# Z_sim_v2.net
KiCad netlist of a schematic drawn in EAGLE
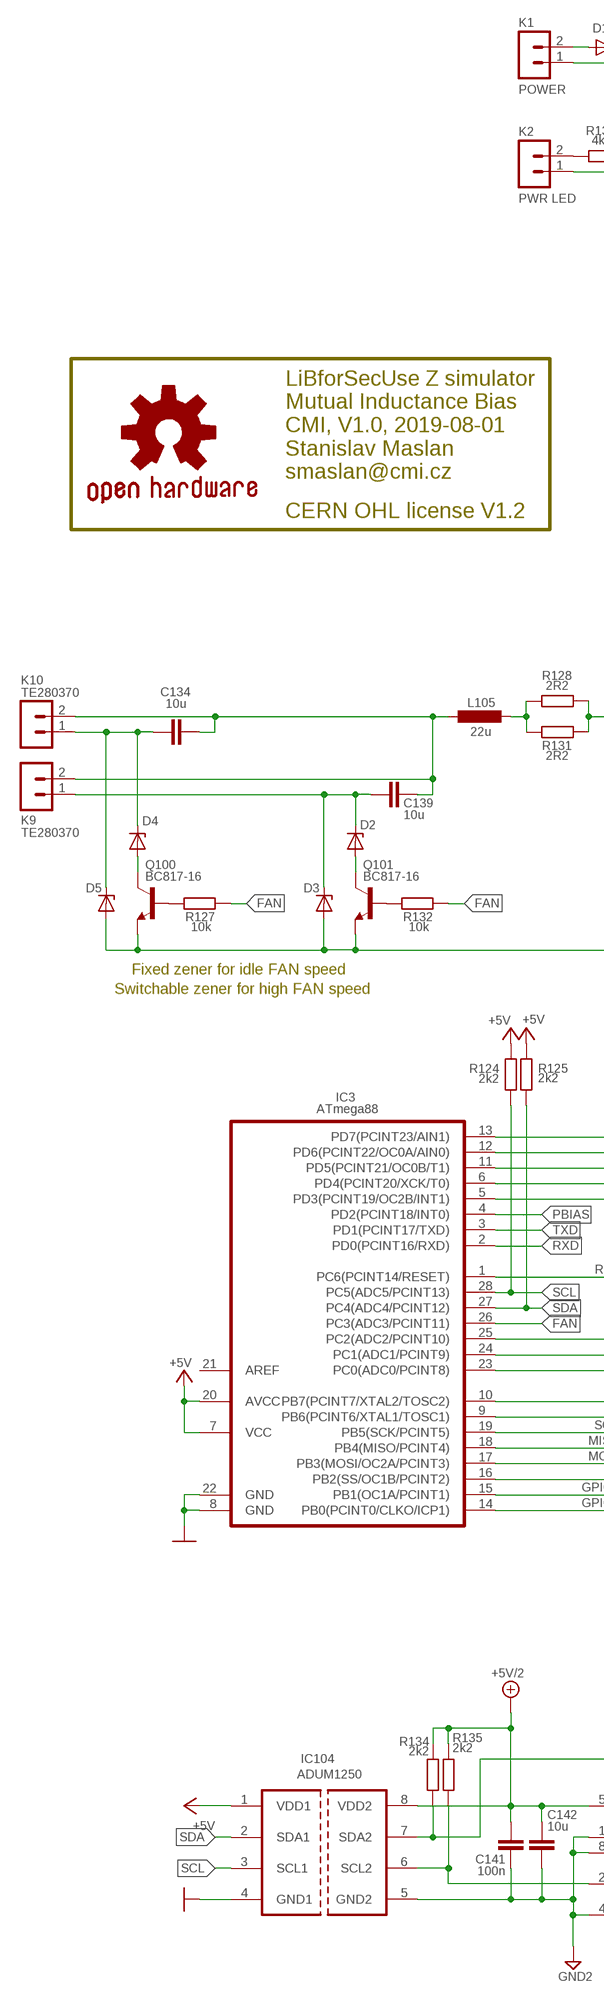
[diagram p0: schematic, sheet 1, part 1 of 2]
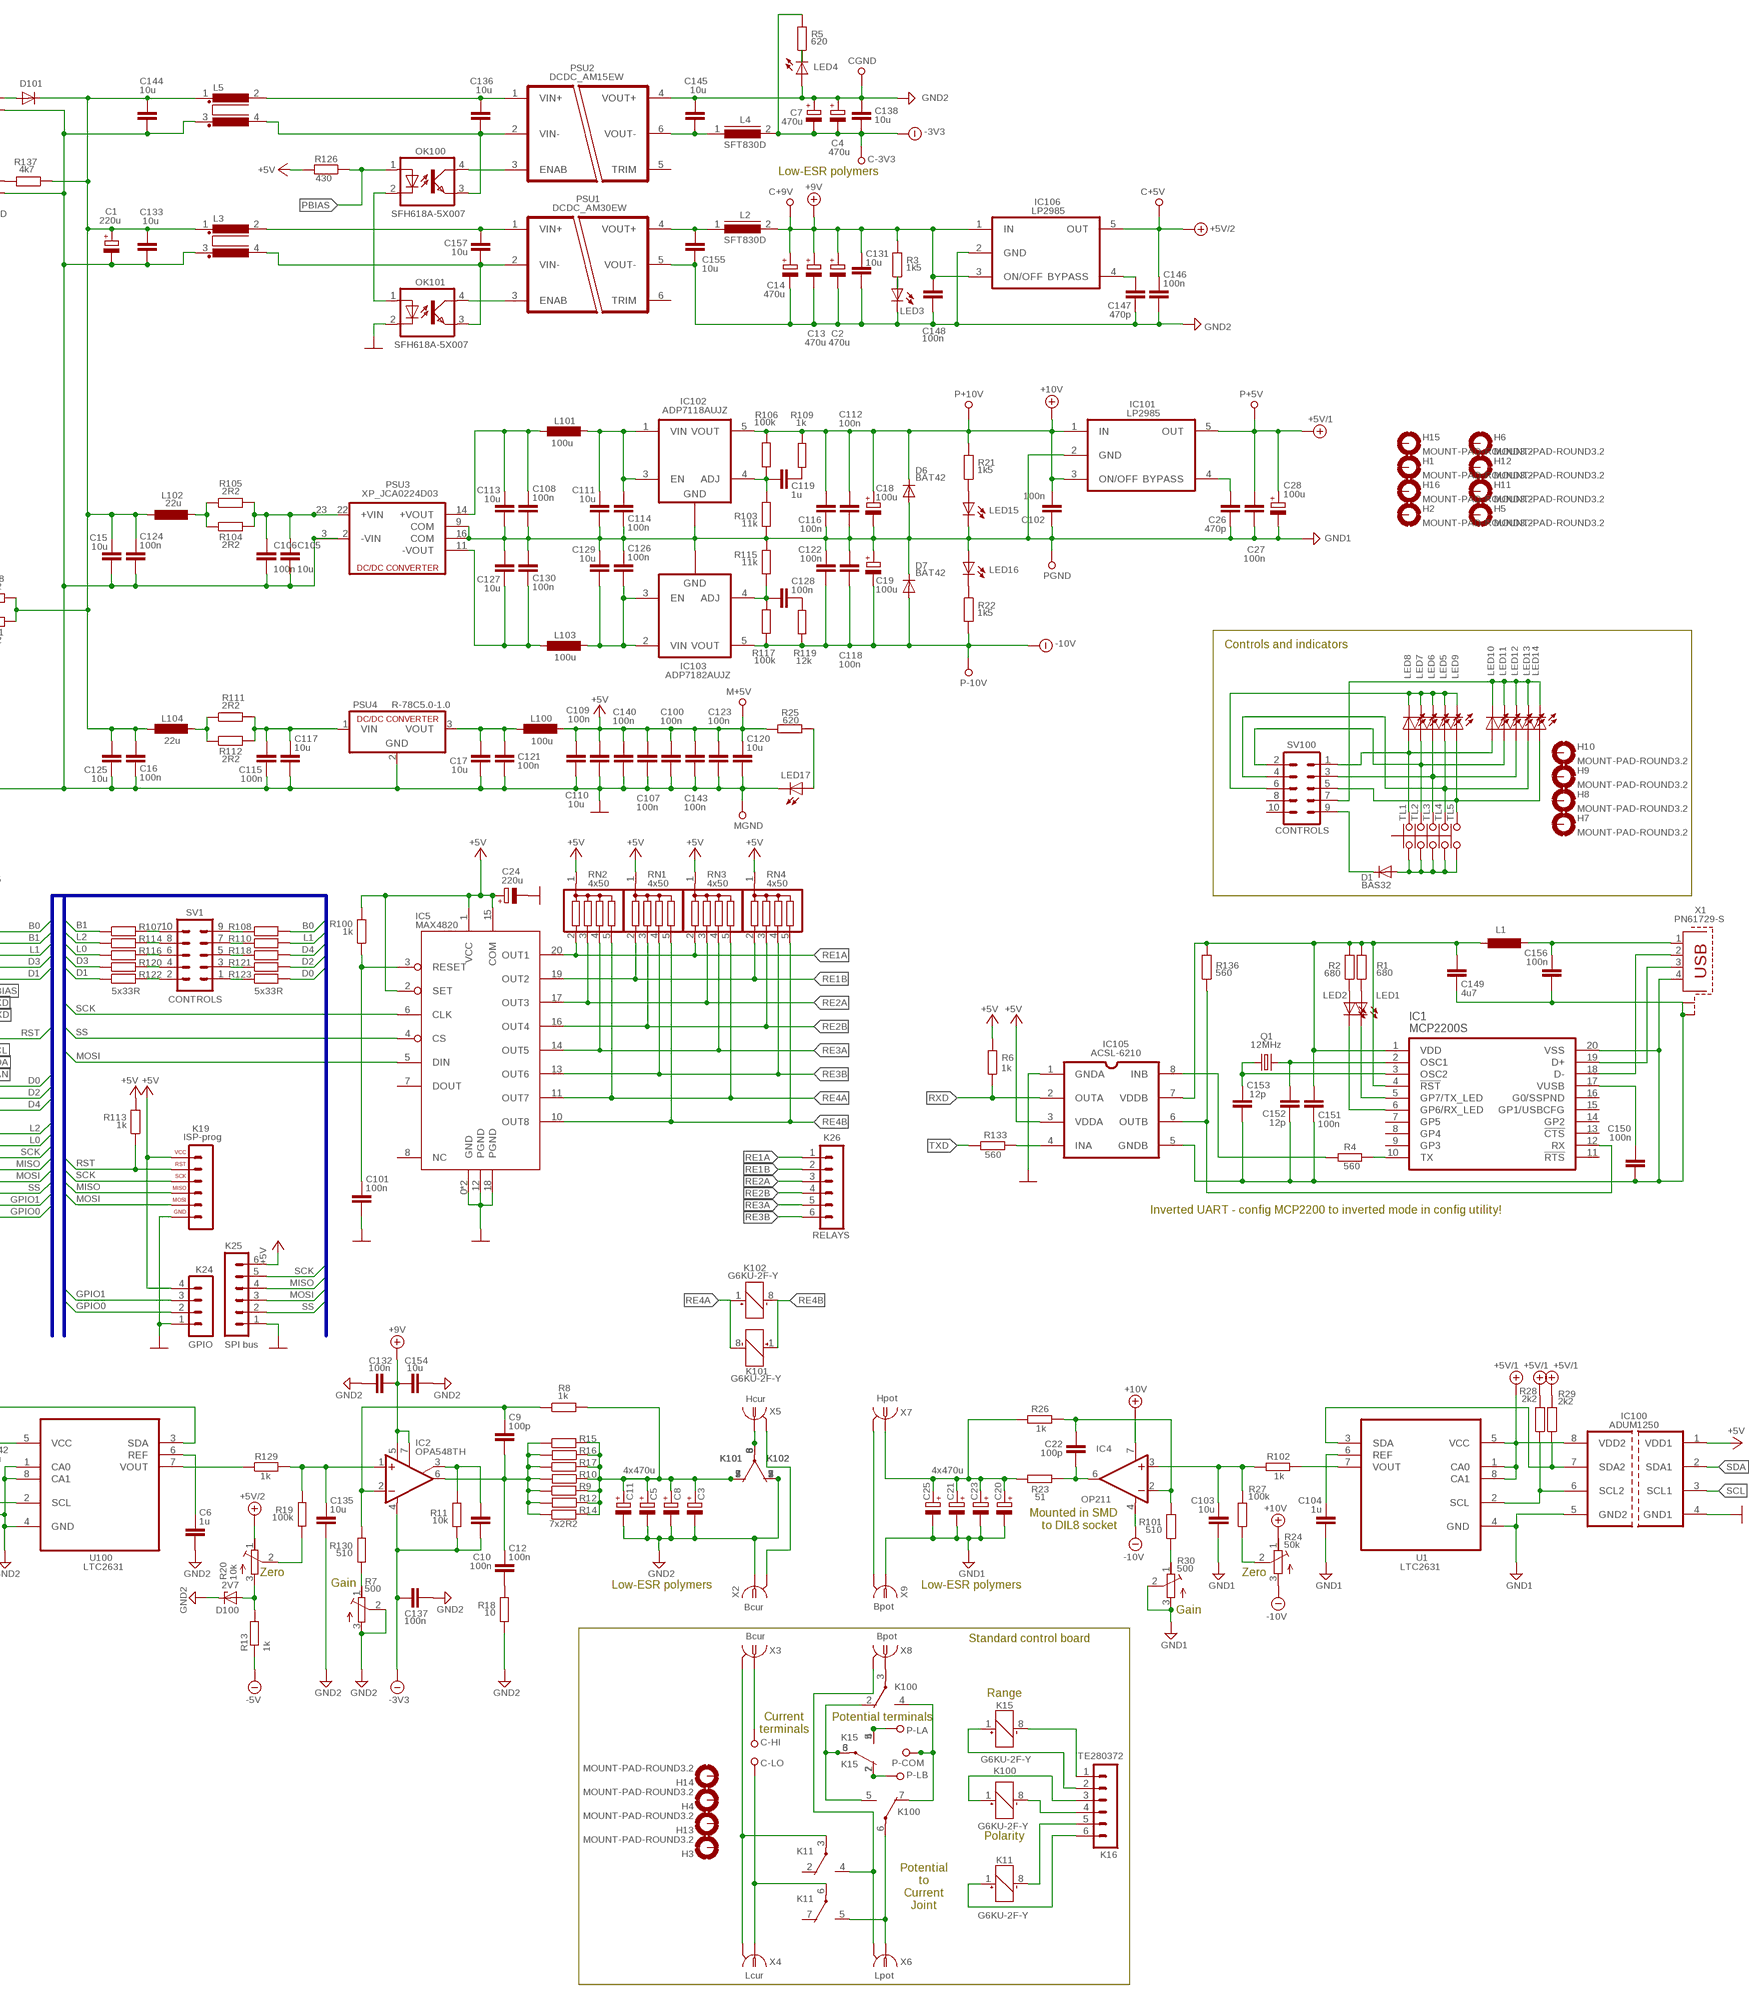
[diagram p1: schematic, sheet 1, part 2 of 2]

(export (version "E")
  (design (tool "Eeschema 10.0.6"))
  (components
    (comp (ref "C+5V")
      (value "SPL")
      (footprint "eagle-import:SP")
      (libsource (lib "eagle-import") (part "SPL"))
    )
    (comp (ref "C+9V")
      (value "SPL")
      (footprint "eagle-import:SP")
      (libsource (lib "eagle-import") (part "SPL"))
    )
    (comp (ref "C-3V3")
      (value "SPL")
      (footprint "eagle-import:SP")
      (libsource (lib "eagle-import") (part "SPL"))
    )
    (comp (ref "C-HI")
      (value "FAST28R")
      (footprint "eagle-import:FAST28_R")
      (libsource (lib "eagle-import") (part "FAST28R"))
    )
    (comp (ref "C-LO")
      (value "FAST28R")
      (footprint "eagle-import:FAST28_R")
      (libsource (lib "eagle-import") (part "FAST28R"))
    )
    (comp (ref "C1")
      (value "220u")
      (footprint "eagle-import:E3,5-8")
      (libsource (lib "eagle-import") (part "CPOL-EUE3.5-8"))
    )
    (comp (ref "C2")
      (value "470u")
      (footprint "eagle-import:E3,5-8")
      (libsource (lib "eagle-import") (part "CPOL-EUE3.5-8"))
    )
    (comp (ref "C3")
      (value "CPOL-EUE3.5-8")
      (footprint "eagle-import:E3,5-8")
      (libsource (lib "eagle-import") (part "CPOL-EUE3.5-8"))
    )
    (comp (ref "C4")
      (value "470u")
      (footprint "eagle-import:E3,5-8")
      (libsource (lib "eagle-import") (part "CPOL-EUE3.5-8"))
    )
    (comp (ref "C5")
      (value "CPOL-EUE3.5-8")
      (footprint "eagle-import:E3,5-8")
      (libsource (lib "eagle-import") (part "CPOL-EUE3.5-8"))
    )
    (comp (ref "C6")
      (value "1u")
      (footprint "eagle-import:X0805")
      (libsource (lib "eagle-import") (part "C-EUX0805"))
    )
    (comp (ref "C7")
      (value "470u")
      (footprint "eagle-import:E3,5-8")
      (libsource (lib "eagle-import") (part "CPOL-EUE3.5-8"))
    )
    (comp (ref "C8")
      (value "CPOL-EUE3.5-8")
      (footprint "eagle-import:E3,5-8")
      (libsource (lib "eagle-import") (part "CPOL-EUE3.5-8"))
    )
    (comp (ref "C9")
      (value "100p")
      (footprint "eagle-import:C025-024X044")
      (libsource (lib "eagle-import") (part "C-EU025-024X044"))
    )
    (comp (ref "C10")
      (value "100n")
      (footprint "eagle-import:X0805")
      (libsource (lib "eagle-import") (part "C-EUX0805"))
    )
    (comp (ref "C11")
      (value "4x470u")
      (footprint "eagle-import:E3,5-8")
      (libsource (lib "eagle-import") (part "CPOL-EUE3.5-8"))
    )
    (comp (ref "C12")
      (value "100n")
      (footprint "eagle-import:C050-024X044")
      (libsource (lib "eagle-import") (part "C-EU050-024X044"))
    )
    (comp (ref "C13")
      (value "470u")
      (footprint "eagle-import:E3,5-8")
      (libsource (lib "eagle-import") (part "CPOL-EUE3.5-8"))
    )
    (comp (ref "C14")
      (value "470u")
      (footprint "eagle-import:E3,5-8")
      (libsource (lib "eagle-import") (part "CPOL-EUE3.5-8"))
    )
    (comp (ref "C15")
      (value "10u")
      (footprint "eagle-import:C1210K")
      (libsource (lib "eagle-import") (part "C-EUC1210K"))
    )
    (comp (ref "C16")
      (value "100n")
      (footprint "eagle-import:X0805")
      (libsource (lib "eagle-import") (part "C-EUX0805"))
    )
    (comp (ref "C17")
      (value "10u")
      (footprint "eagle-import:C1210K")
      (libsource (lib "eagle-import") (part "C-EUC1210K"))
    )
    (comp (ref "C18")
      (value "100u")
      (footprint "eagle-import:E2,5-6")
      (libsource (lib "eagle-import") (part "CPOL-EUE2.5-6"))
    )
    (comp (ref "C19")
      (value "100u")
      (footprint "eagle-import:E2,5-6")
      (libsource (lib "eagle-import") (part "CPOL-EUE2.5-6"))
    )
    (comp (ref "C20")
      (value "CPOL-EUE3.5-8")
      (footprint "eagle-import:E3,5-8")
      (libsource (lib "eagle-import") (part "CPOL-EUE3.5-8"))
    )
    (comp (ref "C21")
      (value "CPOL-EUE3.5-8")
      (footprint "eagle-import:E3,5-8")
      (libsource (lib "eagle-import") (part "CPOL-EUE3.5-8"))
    )
    (comp (ref "C22")
      (value "100p")
      (footprint "eagle-import:C025-024X044")
      (libsource (lib "eagle-import") (part "C-EU025-024X044"))
    )
    (comp (ref "C23")
      (value "CPOL-EUE3.5-8")
      (footprint "eagle-import:E3,5-8")
      (libsource (lib "eagle-import") (part "CPOL-EUE3.5-8"))
    )
    (comp (ref "C24")
      (value "220u")
      (footprint "eagle-import:E3,5-8")
      (libsource (lib "eagle-import") (part "CPOL-EUE3.5-8"))
    )
    (comp (ref "C25")
      (value "4x470u")
      (footprint "eagle-import:E3,5-8")
      (libsource (lib "eagle-import") (part "CPOL-EUE3.5-8"))
    )
    (comp (ref "C26")
      (value "470p")
      (footprint "eagle-import:X0805")
      (libsource (lib "eagle-import") (part "C-EUX0805"))
    )
    (comp (ref "C27")
      (value "100n")
      (footprint "eagle-import:X0805")
      (libsource (lib "eagle-import") (part "C-EUX0805"))
    )
    (comp (ref "C28")
      (value "100u")
      (footprint "eagle-import:E2,5-6")
      (libsource (lib "eagle-import") (part "CPOL-EUE2.5-6"))
    )
    (comp (ref "C100")
      (value "100n")
      (footprint "eagle-import:X0805")
      (libsource (lib "eagle-import") (part "C-EUX0805"))
    )
    (comp (ref "C101")
      (value "100n")
      (footprint "eagle-import:X0805")
      (libsource (lib "eagle-import") (part "C-EUX0805"))
    )
    (comp (ref "C102")
      (value "100n")
      (footprint "eagle-import:X0805")
      (libsource (lib "eagle-import") (part "C-EUX0805"))
    )
    (comp (ref "C103")
      (value "10u")
      (footprint "eagle-import:C1210K")
      (libsource (lib "eagle-import") (part "C-EUC1210K"))
    )
    (comp (ref "C104")
      (value "1u")
      (footprint "eagle-import:X0805")
      (libsource (lib "eagle-import") (part "C-EUX0805"))
    )
    (comp (ref "C105")
      (value "10u")
      (footprint "eagle-import:C1210K")
      (libsource (lib "eagle-import") (part "C-EUC1210K"))
    )
    (comp (ref "C106")
      (value "100n")
      (footprint "eagle-import:X0805")
      (libsource (lib "eagle-import") (part "C-EUX0805"))
    )
    (comp (ref "C107")
      (value "100n")
      (footprint "eagle-import:X0805")
      (libsource (lib "eagle-import") (part "C-EUX0805"))
    )
    (comp (ref "C108")
      (value "100n")
      (footprint "eagle-import:X0805")
      (libsource (lib "eagle-import") (part "C-EUX0805"))
    )
    (comp (ref "C109")
      (value "100n")
      (footprint "eagle-import:X0805")
      (libsource (lib "eagle-import") (part "C-EUX0805"))
    )
    (comp (ref "C110")
      (value "10u")
      (footprint "eagle-import:C1210K")
      (libsource (lib "eagle-import") (part "C-EUC1210K"))
    )
    (comp (ref "C111")
      (value "10u")
      (footprint "eagle-import:C1210K")
      (libsource (lib "eagle-import") (part "C-EUC1210K"))
    )
    (comp (ref "C112")
      (value "100n")
      (footprint "eagle-import:X0805")
      (libsource (lib "eagle-import") (part "C-EUX0805"))
    )
    (comp (ref "C113")
      (value "10u")
      (footprint "eagle-import:C1210K")
      (libsource (lib "eagle-import") (part "C-EUC1210K"))
    )
    (comp (ref "C114")
      (value "100n")
      (footprint "eagle-import:X0805")
      (libsource (lib "eagle-import") (part "C-EUX0805"))
    )
    (comp (ref "C115")
      (value "100n")
      (footprint "eagle-import:X0805")
      (libsource (lib "eagle-import") (part "C-EUX0805"))
    )
    (comp (ref "C116")
      (value "100n")
      (footprint "eagle-import:X0805")
      (libsource (lib "eagle-import") (part "C-EUX0805"))
    )
    (comp (ref "C117")
      (value "10u")
      (footprint "eagle-import:C1210K")
      (libsource (lib "eagle-import") (part "C-EUC1210K"))
    )
    (comp (ref "C118")
      (value "100n")
      (footprint "eagle-import:X0805")
      (libsource (lib "eagle-import") (part "C-EUX0805"))
    )
    (comp (ref "C119")
      (value "1u")
      (footprint "eagle-import:X0805")
      (libsource (lib "eagle-import") (part "C-EUX0805"))
    )
    (comp (ref "C120")
      (value "10u")
      (footprint "eagle-import:C1210K")
      (libsource (lib "eagle-import") (part "C-EUC1210K"))
    )
    (comp (ref "C121")
      (value "100n")
      (footprint "eagle-import:X0805")
      (libsource (lib "eagle-import") (part "C-EUX0805"))
    )
    (comp (ref "C122")
      (value "100n")
      (footprint "eagle-import:X0805")
      (libsource (lib "eagle-import") (part "C-EUX0805"))
    )
    (comp (ref "C123")
      (value "100n")
      (footprint "eagle-import:X0805")
      (libsource (lib "eagle-import") (part "C-EUX0805"))
    )
    (comp (ref "C124")
      (value "100n")
      (footprint "eagle-import:X0805")
      (libsource (lib "eagle-import") (part "C-EUX0805"))
    )
    (comp (ref "C125")
      (value "10u")
      (footprint "eagle-import:C1210K")
      (libsource (lib "eagle-import") (part "C-EUC1210K"))
    )
    (comp (ref "C126")
      (value "100n")
      (footprint "eagle-import:X0805")
      (libsource (lib "eagle-import") (part "C-EUX0805"))
    )
    (comp (ref "C127")
      (value "10u")
      (footprint "eagle-import:C1210K")
      (libsource (lib "eagle-import") (part "C-EUC1210K"))
    )
    (comp (ref "C128")
      (value "100n")
      (footprint "eagle-import:X0805")
      (libsource (lib "eagle-import") (part "C-EUX0805"))
    )
    (comp (ref "C129")
      (value "10u")
      (footprint "eagle-import:C1210K")
      (libsource (lib "eagle-import") (part "C-EUC1210K"))
    )
    (comp (ref "C130")
      (value "100n")
      (footprint "eagle-import:X0805")
      (libsource (lib "eagle-import") (part "C-EUX0805"))
    )
    (comp (ref "C131")
      (value "10u")
      (footprint "eagle-import:C1210K")
      (libsource (lib "eagle-import") (part "C-EUC1210K"))
    )
    (comp (ref "C132")
      (value "100n")
      (footprint "eagle-import:X0805")
      (libsource (lib "eagle-import") (part "C-EUX0805"))
    )
    (comp (ref "C133")
      (value "10u")
      (footprint "eagle-import:C1210K")
      (libsource (lib "eagle-import") (part "C-EUC1210K"))
    )
    (comp (ref "C134")
      (value "10u")
      (footprint "eagle-import:C1210K")
      (libsource (lib "eagle-import") (part "C-EUC1210K"))
    )
    (comp (ref "C135")
      (value "10u")
      (footprint "eagle-import:C1210K")
      (libsource (lib "eagle-import") (part "C-EUC1210K"))
    )
    (comp (ref "C136")
      (value "10u")
      (footprint "eagle-import:C1210K")
      (libsource (lib "eagle-import") (part "C-EUC1210K"))
    )
    (comp (ref "C137")
      (value "100n")
      (footprint "eagle-import:X0805")
      (libsource (lib "eagle-import") (part "C-EUX0805"))
    )
    (comp (ref "C138")
      (value "10u")
      (footprint "eagle-import:C1210K")
      (libsource (lib "eagle-import") (part "C-EUC1210K"))
    )
    (comp (ref "C139")
      (value "10u")
      (footprint "eagle-import:C1210K")
      (libsource (lib "eagle-import") (part "C-EUC1210K"))
    )
    (comp (ref "C140")
      (value "100n")
      (footprint "eagle-import:X0805")
      (libsource (lib "eagle-import") (part "C-EUX0805"))
    )
    (comp (ref "C141")
      (value "100n")
      (footprint "eagle-import:X0805")
      (libsource (lib "eagle-import") (part "C-EUX0805"))
    )
    (comp (ref "C142")
      (value "10u")
      (footprint "eagle-import:C1210K")
      (libsource (lib "eagle-import") (part "C-EUC1210K"))
    )
    (comp (ref "C143")
      (value "100n")
      (footprint "eagle-import:X0805")
      (libsource (lib "eagle-import") (part "C-EUX0805"))
    )
    (comp (ref "C144")
      (value "10u")
      (footprint "eagle-import:C1210K")
      (libsource (lib "eagle-import") (part "C-EUC1210K"))
    )
    (comp (ref "C145")
      (value "10u")
      (footprint "eagle-import:C1210K")
      (libsource (lib "eagle-import") (part "C-EUC1210K"))
    )
    (comp (ref "C146")
      (value "100n")
      (footprint "eagle-import:X0805")
      (libsource (lib "eagle-import") (part "C-EUX0805"))
    )
    (comp (ref "C147")
      (value "470p")
      (footprint "eagle-import:X0805")
      (libsource (lib "eagle-import") (part "C-EUX0805"))
    )
    (comp (ref "C148")
      (value "100n")
      (footprint "eagle-import:X0805")
      (libsource (lib "eagle-import") (part "C-EUX0805"))
    )
    (comp (ref "C149")
      (value "4u7")
      (footprint "eagle-import:C1210K")
      (libsource (lib "eagle-import") (part "C-EUC1210K"))
    )
    (comp (ref "C150")
      (value "100n")
      (footprint "eagle-import:X0805")
      (libsource (lib "eagle-import") (part "C0805"))
    )
    (comp (ref "C151")
      (value "100n")
      (footprint "eagle-import:X0805")
      (libsource (lib "eagle-import") (part "C0805"))
    )
    (comp (ref "C152")
      (value "12p")
      (footprint "eagle-import:X0805")
      (libsource (lib "eagle-import") (part "C0805"))
    )
    (comp (ref "C153")
      (value "12p")
      (footprint "eagle-import:X0805")
      (libsource (lib "eagle-import") (part "C0805"))
    )
    (comp (ref "C154")
      (value "10u")
      (footprint "eagle-import:C1210K")
      (libsource (lib "eagle-import") (part "C-EUC1210K"))
    )
    (comp (ref "C155")
      (value "10u")
      (footprint "eagle-import:C1210K")
      (libsource (lib "eagle-import") (part "C-EUC1210K"))
    )
    (comp (ref "C156")
      (value "100n")
      (footprint "eagle-import:X0805")
      (libsource (lib "eagle-import") (part "C0805"))
    )
    (comp (ref "C157")
      (value "10u")
      (footprint "eagle-import:C1210K")
      (libsource (lib "eagle-import") (part "C-EUC1210K"))
    )
    (comp (ref "CGND")
      (value "SPL")
      (footprint "eagle-import:SP")
      (libsource (lib "eagle-import") (part "SPL"))
    )
    (comp (ref "D1")
      (value "BAS32")
      (footprint "eagle-import:SOD80C")
      (libsource (lib "eagle-import") (part "BAS32"))
    )
    (comp (ref "D2")
      (value "ZENER-DIODEZD-2.5")
      (footprint "eagle-import:ZDIO-2.5")
      (libsource (lib "eagle-import") (part "ZENER-DIODEZD-2.5"))
    )
    (comp (ref "D3")
      (value "ZENER-DIODEZD-2.5")
      (footprint "eagle-import:ZDIO-2.5")
      (libsource (lib "eagle-import") (part "ZENER-DIODEZD-2.5"))
    )
    (comp (ref "D4")
      (value "ZENER-DIODEZD-2.5")
      (footprint "eagle-import:ZDIO-2.5")
      (libsource (lib "eagle-import") (part "ZENER-DIODEZD-2.5"))
    )
    (comp (ref "D5")
      (value "ZENER-DIODEZD-2.5")
      (footprint "eagle-import:ZDIO-2.5")
      (libsource (lib "eagle-import") (part "ZENER-DIODEZD-2.5"))
    )
    (comp (ref "D6")
      (value "BAT42")
      (footprint "eagle-import:SOD80C")
      (libsource (lib "eagle-import") (part "DIODE-SOD80C"))
    )
    (comp (ref "D7")
      (value "BAT42")
      (footprint "eagle-import:SOD80C")
      (libsource (lib "eagle-import") (part "DIODE-SOD80C"))
    )
    (comp (ref "D100")
      (value "2V7")
      (footprint "eagle-import:SOD80C")
      (libsource (lib "eagle-import") (part "ZENER-DIODESOD80C"))
    )
    (comp (ref "D101")
      (value "DIODE-MELF-MLL41")
      (footprint "eagle-import:MELF-MLL41")
      (libsource (lib "eagle-import") (part "DIODE-MELF-MLL41"))
    )
    (comp (ref "GOLD_ORB_SM1")
      (value "OSHWLOGO_GOLD_ORB_MED")
      (footprint "eagle-import:OSHW1")
      (libsource (lib "eagle-import") (part "OSHWLOGO_GOLD_ORB_MED"))
    )
    (comp (ref "H1")
      (value "MOUNT-PAD-ROUND3.2")
      (footprint "eagle-import:3,2-PAD")
      (libsource (lib "eagle-import") (part "MOUNT-PAD-ROUND3.2"))
    )
    (comp (ref "H2")
      (value "MOUNT-PAD-ROUND3.2")
      (footprint "eagle-import:3,2-PAD")
      (libsource (lib "eagle-import") (part "MOUNT-PAD-ROUND3.2"))
    )
    (comp (ref "H3")
      (value "MOUNT-PAD-ROUND3.2")
      (footprint "eagle-import:3,2-PAD")
      (libsource (lib "eagle-import") (part "MOUNT-PAD-ROUND3.2"))
    )
    (comp (ref "H4")
      (value "MOUNT-PAD-ROUND3.2")
      (footprint "eagle-import:3,2-PAD")
      (libsource (lib "eagle-import") (part "MOUNT-PAD-ROUND3.2"))
    )
    (comp (ref "H5")
      (value "MOUNT-PAD-ROUND3.2")
      (footprint "eagle-import:3,2-PAD")
      (libsource (lib "eagle-import") (part "MOUNT-PAD-ROUND3.2"))
    )
    (comp (ref "H6")
      (value "MOUNT-PAD-ROUND3.2")
      (footprint "eagle-import:3,2-PAD")
      (libsource (lib "eagle-import") (part "MOUNT-PAD-ROUND3.2"))
    )
    (comp (ref "H7")
      (value "MOUNT-PAD-ROUND3.2")
      (footprint "eagle-import:3,2-PAD")
      (libsource (lib "eagle-import") (part "MOUNT-PAD-ROUND3.2"))
    )
    (comp (ref "H8")
      (value "MOUNT-PAD-ROUND3.2")
      (footprint "eagle-import:3,2-PAD")
      (libsource (lib "eagle-import") (part "MOUNT-PAD-ROUND3.2"))
    )
    (comp (ref "H9")
      (value "MOUNT-PAD-ROUND3.2")
      (footprint "eagle-import:3,2-PAD")
      (libsource (lib "eagle-import") (part "MOUNT-PAD-ROUND3.2"))
    )
    (comp (ref "H10")
      (value "MOUNT-PAD-ROUND3.2")
      (footprint "eagle-import:3,2-PAD")
      (libsource (lib "eagle-import") (part "MOUNT-PAD-ROUND3.2"))
    )
    (comp (ref "H11")
      (value "MOUNT-PAD-ROUND3.2")
      (footprint "eagle-import:3,2-PAD")
      (libsource (lib "eagle-import") (part "MOUNT-PAD-ROUND3.2"))
    )
    (comp (ref "H12")
      (value "MOUNT-PAD-ROUND3.2")
      (footprint "eagle-import:3,2-PAD")
      (libsource (lib "eagle-import") (part "MOUNT-PAD-ROUND3.2"))
    )
    (comp (ref "H13")
      (value "MOUNT-PAD-ROUND3.2")
      (footprint "eagle-import:3,2-PAD")
      (libsource (lib "eagle-import") (part "MOUNT-PAD-ROUND3.2"))
    )
    (comp (ref "H14")
      (value "MOUNT-PAD-ROUND3.2")
      (footprint "eagle-import:3,2-PAD")
      (libsource (lib "eagle-import") (part "MOUNT-PAD-ROUND3.2"))
    )
    (comp (ref "H15")
      (value "MOUNT-PAD-ROUND3.2")
      (footprint "eagle-import:3,2-PAD")
      (libsource (lib "eagle-import") (part "MOUNT-PAD-ROUND3.2"))
    )
    (comp (ref "H16")
      (value "MOUNT-PAD-ROUND3.2")
      (footprint "eagle-import:3,2-PAD")
      (libsource (lib "eagle-import") (part "MOUNT-PAD-ROUND3.2"))
    )
    (comp (ref "IC1")
      (value "MCP2200S")
      (footprint "eagle-import:SOIC20W")
      (libsource (lib "eagle-import") (part "MCP2200S"))
    )
    (comp (ref "IC2")
      (value "OPA548TH")
      (footprint "eagle-import:TO220-7H")
      (libsource (lib "eagle-import") (part "OPA548TH"))
    )
    (comp (ref "IC3")
      (value "ATmega88")
      (footprint "eagle-import:DIL28")
      (libsource (lib "eagle-import") (part "ATMEGA88P"))
    )
    (comp (ref "IC4")
      (value "OP211")
      (footprint "eagle-import:DIL08")
      (libsource (lib "eagle-import") (part "OPA650P"))
    )
    (comp (ref "IC5")
      (value "MAX4820")
      (footprint "eagle-import:TSSOP20")
      (libsource (lib "eagle-import") (part "MAX4820_TSSOP"))
    )
    (comp (ref "IC100")
      (value "ADUM1250")
      (footprint "eagle-import:SO8")
      (libsource (lib "eagle-import") (part "ADUM1250"))
    )
    (comp (ref "IC101")
      (value "LP2985")
      (footprint "eagle-import:SOT23-5")
      (libsource (lib "eagle-import") (part "LP2985"))
    )
    (comp (ref "IC102")
      (value "ADP7118AUJZ")
      (footprint "eagle-import:SOT23-5")
      (libsource (lib "eagle-import") (part "ADP7118AUJZ"))
    )
    (comp (ref "IC103")
      (value "ADP7182AUJZ")
      (footprint "eagle-import:SOT23-5")
      (libsource (lib "eagle-import") (part "ADP7182AUJZ"))
    )
    (comp (ref "IC104")
      (value "ADUM1250")
      (footprint "eagle-import:SO8")
      (libsource (lib "eagle-import") (part "ADUM1250"))
    )
    (comp (ref "IC105")
      (value "ACSL-6210")
      (footprint "eagle-import:SO8")
      (libsource (lib "eagle-import") (part "ACSL-6210"))
    )
    (comp (ref "IC106")
      (value "LP2985")
      (footprint "eagle-import:SOT23-5")
      (libsource (lib "eagle-import") (part "LP2985"))
    )
    (comp (ref "K1")
      (value "POWER")
      (footprint "eagle-import:TE280370")
      (libsource (lib "eagle-import") (part "TE280370"))
    )
    (comp (ref "K2")
      (value "PWR LED")
      (footprint "eagle-import:TE280370")
      (libsource (lib "eagle-import") (part "TE280370"))
    )
    (comp (ref "K9")
      (value "TE280370")
      (footprint "eagle-import:TE280370")
      (libsource (lib "eagle-import") (part "TE280370"))
    )
    (comp (ref "K10")
      (value "TE280370")
      (footprint "eagle-import:TE280370")
      (libsource (lib "eagle-import") (part "TE280370"))
    )
    (comp (ref "K11")
      (value "G6KU-2F-Y")
      (footprint "eagle-import:G6KU-2F-Y")
      (fields (field (name "MF") "OMRON COMPONENTS USA") (field (name "MPN") "G6KU-2F-Y DC3"))
      (libsource (lib "eagle-import") (part "G6KU-2F-Y"))
    )
    (comp (ref "K15")
      (value "G6KU-2F-Y")
      (footprint "eagle-import:G6KU-2F-Y")
      (fields (field (name "MF") "OMRON COMPONENTS USA") (field (name "MPN") "G6KU-2F-Y DC3"))
      (libsource (lib "eagle-import") (part "G6KU-2F-Y"))
    )
    (comp (ref "K16")
      (value "TE280372")
      (footprint "eagle-import:TE280372")
      (libsource (lib "eagle-import") (part "TE280372"))
    )
    (comp (ref "K19")
      (value "ISP-prog")
      (footprint "eagle-import:SIL6")
      (libsource (lib "eagle-import") (part "AVR_SPI"))
    )
    (comp (ref "K24")
      (value "GPIO")
      (footprint "eagle-import:TE280371")
      (libsource (lib "eagle-import") (part "TE280371"))
    )
    (comp (ref "K25")
      (value "SPI bus")
      (footprint "eagle-import:TE280372")
      (libsource (lib "eagle-import") (part "TE280372"))
    )
    (comp (ref "K26")
      (value "RELAYS")
      (footprint "eagle-import:TE280372")
      (libsource (lib "eagle-import") (part "TE280372"))
    )
    (comp (ref "K100")
      (value "G6KU-2F-Y")
      (footprint "eagle-import:G6KU-2F-Y")
      (fields (field (name "MF") "OMRON COMPONENTS USA") (field (name "MPN") "G6KU-2F-Y DC3"))
      (libsource (lib "eagle-import") (part "G6KU-2F-Y"))
    )
    (comp (ref "K101")
      (value "G6KU-2F-Y")
      (footprint "eagle-import:G6KU-2F-Y")
      (fields (field (name "MF") "OMRON COMPONENTS USA") (field (name "MPN") "G6KU-2F-Y DC3"))
      (libsource (lib "eagle-import") (part "G6KU-2F-Y"))
    )
    (comp (ref "K102")
      (value "G6KU-2F-Y")
      (footprint "eagle-import:G6KU-2F-Y")
      (fields (field (name "MF") "OMRON COMPONENTS USA") (field (name "MPN") "G6KU-2F-Y DC3"))
      (libsource (lib "eagle-import") (part "G6KU-2F-Y"))
    )
    (comp (ref "L1")
      (value "L-EU0204/5")
      (footprint "eagle-import:0204_5")
      (libsource (lib "eagle-import") (part "L-EU0204/5"))
    )
    (comp (ref "L2")
      (value "SFT830D")
      (footprint "eagle-import:SFT830D")
      (libsource (lib "eagle-import") (part "SFT830D"))
    )
    (comp (ref "L3")
      (value "R1405UB1/2")
      (footprint "eagle-import:B1_2")
      (libsource (lib "eagle-import") (part "R1405UB1/2"))
    )
    (comp (ref "L4")
      (value "SFT830D")
      (footprint "eagle-import:SFT830D")
      (libsource (lib "eagle-import") (part "SFT830D"))
    )
    (comp (ref "L5")
      (value "R1405UB1/2")
      (footprint "eagle-import:B1_2")
      (libsource (lib "eagle-import") (part "R1405UB1/2"))
    )
    (comp (ref "L100")
      (value "100u")
      (footprint "eagle-import:L1812")
      (libsource (lib "eagle-import") (part "L-EUL1812"))
    )
    (comp (ref "L101")
      (value "100u")
      (footprint "eagle-import:L1812")
      (libsource (lib "eagle-import") (part "L-EUL1812"))
    )
    (comp (ref "L102")
      (value "22u")
      (footprint "eagle-import:L1812")
      (libsource (lib "eagle-import") (part "L-EUL1812"))
    )
    (comp (ref "L103")
      (value "100u")
      (footprint "eagle-import:L1812")
      (libsource (lib "eagle-import") (part "L-EUL1812"))
    )
    (comp (ref "L104")
      (value "22u")
      (footprint "eagle-import:L1812")
      (libsource (lib "eagle-import") (part "L-EUL1812"))
    )
    (comp (ref "L105")
      (value "22u")
      (footprint "eagle-import:L1812")
      (libsource (lib "eagle-import") (part "L-EUL1812"))
    )
    (comp (ref "LED1")
      (value "LEDCHIP-LED0603")
      (footprint "eagle-import:CHIP-LED0603")
      (libsource (lib "eagle-import") (part "LEDCHIP-LED0603"))
    )
    (comp (ref "LED2")
      (value "LEDCHIP-LED0603")
      (footprint "eagle-import:CHIP-LED0603")
      (libsource (lib "eagle-import") (part "LEDCHIP-LED0603"))
    )
    (comp (ref "LED3")
      (value "LEDCHIP-LED0603")
      (footprint "eagle-import:CHIP-LED0603")
      (libsource (lib "eagle-import") (part "LEDCHIP-LED0603"))
    )
    (comp (ref "LED4")
      (value "LEDCHIP-LED0603")
      (footprint "eagle-import:CHIP-LED0603")
      (libsource (lib "eagle-import") (part "LEDCHIP-LED0603"))
    )
    (comp (ref "LED5")
      (value "LED3MM")
      (footprint "eagle-import:LED3MM")
      (libsource (lib "eagle-import") (part "LED3MM"))
    )
    (comp (ref "LED6")
      (value "LED3MM")
      (footprint "eagle-import:LED3MM")
      (libsource (lib "eagle-import") (part "LED3MM"))
    )
    (comp (ref "LED7")
      (value "LED3MM")
      (footprint "eagle-import:LED3MM")
      (libsource (lib "eagle-import") (part "LED3MM"))
    )
    (comp (ref "LED8")
      (value "LED3MM")
      (footprint "eagle-import:LED3MM")
      (libsource (lib "eagle-import") (part "LED3MM"))
    )
    (comp (ref "LED9")
      (value "LED3MM")
      (footprint "eagle-import:LED3MM")
      (libsource (lib "eagle-import") (part "LED3MM"))
    )
    (comp (ref "LED10")
      (value "LED3MM")
      (footprint "eagle-import:LED3MM")
      (libsource (lib "eagle-import") (part "LED3MM"))
    )
    (comp (ref "LED11")
      (value "LED3MM")
      (footprint "eagle-import:LED3MM")
      (libsource (lib "eagle-import") (part "LED3MM"))
    )
    (comp (ref "LED12")
      (value "LED3MM")
      (footprint "eagle-import:LED3MM")
      (libsource (lib "eagle-import") (part "LED3MM"))
    )
    (comp (ref "LED13")
      (value "LED3MM")
      (footprint "eagle-import:LED3MM")
      (libsource (lib "eagle-import") (part "LED3MM"))
    )
    (comp (ref "LED14")
      (value "LED3MM")
      (footprint "eagle-import:LED3MM")
      (libsource (lib "eagle-import") (part "LED3MM"))
    )
    (comp (ref "LED15")
      (value "LEDCHIP-LED0603")
      (footprint "eagle-import:CHIP-LED0603")
      (libsource (lib "eagle-import") (part "LEDCHIP-LED0603"))
    )
    (comp (ref "LED16")
      (value "LEDCHIP-LED0603")
      (footprint "eagle-import:CHIP-LED0603")
      (libsource (lib "eagle-import") (part "LEDCHIP-LED0603"))
    )
    (comp (ref "LED17")
      (value "LEDCHIP-LED0603")
      (footprint "eagle-import:CHIP-LED0603")
      (libsource (lib "eagle-import") (part "LEDCHIP-LED0603"))
    )
    (comp (ref "M+5V")
      (value "SPL")
      (footprint "eagle-import:SP")
      (libsource (lib "eagle-import") (part "SPL"))
    )
    (comp (ref "MGND")
      (value "SPL")
      (footprint "eagle-import:SP")
      (libsource (lib "eagle-import") (part "SPL"))
    )
    (comp (ref "OK100")
      (value "SFH618A-5X007")
      (footprint "eagle-import:SMD4-7")
      (libsource (lib "eagle-import") (part "SFH618?A-5X007"))
    )
    (comp (ref "OK101")
      (value "SFH618A-5X007")
      (footprint "eagle-import:SMD4-7")
      (libsource (lib "eagle-import") (part "SFH618?A-5X007"))
    )
    (comp (ref "P+5V")
      (value "SPL")
      (footprint "eagle-import:SP")
      (libsource (lib "eagle-import") (part "SPL"))
    )
    (comp (ref "P+10V")
      (value "SPL")
      (footprint "eagle-import:SP")
      (libsource (lib "eagle-import") (part "SPL"))
    )
    (comp (ref "P-10V")
      (value "SPL")
      (footprint "eagle-import:SP")
      (libsource (lib "eagle-import") (part "SPL"))
    )
    (comp (ref "P-COM")
      (value "FAST28R")
      (footprint "eagle-import:FAST28_R")
      (libsource (lib "eagle-import") (part "FAST28R"))
    )
    (comp (ref "P-LA")
      (value "FAST28R")
      (footprint "eagle-import:FAST28_R")
      (libsource (lib "eagle-import") (part "FAST28R"))
    )
    (comp (ref "P-LB")
      (value "FAST28R")
      (footprint "eagle-import:FAST28_R")
      (libsource (lib "eagle-import") (part "FAST28R"))
    )
    (comp (ref "PGND")
      (value "SPL")
      (footprint "eagle-import:SP")
      (libsource (lib "eagle-import") (part "SPL"))
    )
    (comp (ref "PSU1")
      (value "DCDC_AM30EW")
      (footprint "eagle-import:DCDC_AM30EW")
      (libsource (lib "eagle-import") (part "DCDC_AM30EW"))
    )
    (comp (ref "PSU2")
      (value "DCDC_AM15EW")
      (footprint "eagle-import:DCDC_AM15EW")
      (libsource (lib "eagle-import") (part "DCDC_AM15EW"))
    )
    (comp (ref "PSU3")
      (value "XP_JCA0224D03")
      (footprint "eagle-import:DCDC_XP_JCA_SYMOUT")
      (libsource (lib "eagle-import") (part "XP_JCA0224D03"))
    )
    (comp (ref "PSU4")
      (value "R-78C5.0-1.0")
      (footprint "eagle-import:SIP3")
      (libsource (lib "eagle-import") (part "R-78C-1.05.0"))
    )
    (comp (ref "Q1")
      (value "12MHz")
      (footprint "eagle-import:HC49_S")
      (libsource (lib "eagle-import") (part "CRYSTALHC49S"))
    )
    (comp (ref "Q100")
      (value "BC817-16")
      (footprint "eagle-import:SOT23-BEC")
      (libsource (lib "eagle-import") (part "BC817SMD-16LT1"))
    )
    (comp (ref "Q101")
      (value "BC817-16")
      (footprint "eagle-import:SOT23-BEC")
      (libsource (lib "eagle-import") (part "BC817SMD-16LT1"))
    )
    (comp (ref "R1")
      (value "680")
      (footprint "eagle-import:X0805")
      (libsource (lib "eagle-import") (part "R0805"))
    )
    (comp (ref "R2")
      (value "680")
      (footprint "eagle-import:X0805")
      (libsource (lib "eagle-import") (part "R0805"))
    )
    (comp (ref "R3")
      (value "1k5")
      (footprint "eagle-import:X0805")
      (libsource (lib "eagle-import") (part "R0805"))
    )
    (comp (ref "R4")
      (value "560")
      (footprint "eagle-import:X0805")
      (libsource (lib "eagle-import") (part "R0805"))
    )
    (comp (ref "R5")
      (value "620")
      (footprint "eagle-import:X0805")
      (libsource (lib "eagle-import") (part "R0805"))
    )
    (comp (ref "R6")
      (value "1k")
      (footprint "eagle-import:X0805")
      (libsource (lib "eagle-import") (part "R0805"))
    )
    (comp (ref "R7")
      (value "500")
      (footprint "eagle-import:RTRIMT93YB")
      (libsource (lib "eagle-import") (part "R-TRIMMT93YB"))
    )
    (comp (ref "R8")
      (value "1k")
      (footprint "eagle-import:0207_2V")
      (libsource (lib "eagle-import") (part "R-EU_0207/2V"))
    )
    (comp (ref "R9")
      (value "R-EU_0207/2V")
      (footprint "eagle-import:0207_2V")
      (libsource (lib "eagle-import") (part "R-EU_0207/2V"))
    )
    (comp (ref "R10")
      (value "R-EU_0207/2V")
      (footprint "eagle-import:0207_2V")
      (libsource (lib "eagle-import") (part "R-EU_0207/2V"))
    )
    (comp (ref "R11")
      (value "10k")
      (footprint "eagle-import:X0805")
      (libsource (lib "eagle-import") (part "R-EU_X0805"))
    )
    (comp (ref "R12")
      (value "7x2R2")
      (footprint "eagle-import:0207_2V")
      (libsource (lib "eagle-import") (part "R-EU_0207/2V"))
    )
    (comp (ref "R13")
      (value "1k")
      (footprint "eagle-import:X0805")
      (libsource (lib "eagle-import") (part "R-EU_X0805"))
    )
    (comp (ref "R14")
      (value "R-EU_0207/2V")
      (footprint "eagle-import:0207_2V")
      (libsource (lib "eagle-import") (part "R-EU_0207/2V"))
    )
    (comp (ref "R15")
      (value "R-EU_0207/2V")
      (footprint "eagle-import:0207_2V")
      (libsource (lib "eagle-import") (part "R-EU_0207/2V"))
    )
    (comp (ref "R16")
      (value "R-EU_0207/2V")
      (footprint "eagle-import:0207_2V")
      (libsource (lib "eagle-import") (part "R-EU_0207/2V"))
    )
    (comp (ref "R17")
      (value "R-EU_0207/2V")
      (footprint "eagle-import:0207_2V")
      (libsource (lib "eagle-import") (part "R-EU_0207/2V"))
    )
    (comp (ref "R18")
      (value "10")
      (footprint "eagle-import:0207_2V")
      (libsource (lib "eagle-import") (part "R-EU_0207/2V"))
    )
    (comp (ref "R19")
      (value "100k")
      (footprint "eagle-import:0204V")
      (libsource (lib "eagle-import") (part "R-EU_0204/2V"))
    )
    (comp (ref "R20")
      (value "10k")
      (footprint "eagle-import:RTRIMT93YB")
      (libsource (lib "eagle-import") (part "R-TRIMMT93YB"))
    )
    (comp (ref "R21")
      (value "1k5")
      (footprint "eagle-import:X0805")
      (libsource (lib "eagle-import") (part "R0805"))
    )
    (comp (ref "R22")
      (value "1k5")
      (footprint "eagle-import:X0805")
      (libsource (lib "eagle-import") (part "R0805"))
    )
    (comp (ref "R23")
      (value "51")
      (footprint "eagle-import:0207_2V")
      (libsource (lib "eagle-import") (part "R-EU_0207/2V"))
    )
    (comp (ref "R24")
      (value "50k")
      (footprint "eagle-import:RTRIMT93YB")
      (libsource (lib "eagle-import") (part "R-TRIMMT93YB"))
    )
    (comp (ref "R25")
      (value "620")
      (footprint "eagle-import:X0805")
      (libsource (lib "eagle-import") (part "R0805"))
    )
    (comp (ref "R26")
      (value "1k")
      (footprint "eagle-import:0207_2V")
      (libsource (lib "eagle-import") (part "R-EU_0207/2V"))
    )
    (comp (ref "R27")
      (value "100k")
      (footprint "eagle-import:0204V")
      (libsource (lib "eagle-import") (part "R-EU_0204/2V"))
    )
    (comp (ref "R28")
      (value "2k2")
      (footprint "eagle-import:X0805")
      (libsource (lib "eagle-import") (part "R-EU_X0805"))
    )
    (comp (ref "R29")
      (value "2k2")
      (footprint "eagle-import:X0805")
      (libsource (lib "eagle-import") (part "R-EU_X0805"))
    )
    (comp (ref "R30")
      (value "500")
      (footprint "eagle-import:RTRIMT93YB")
      (libsource (lib "eagle-import") (part "R-TRIMMT93YB"))
    )
    (comp (ref "R100")
      (value "1k")
      (footprint "eagle-import:X0805")
      (libsource (lib "eagle-import") (part "R0805"))
    )
    (comp (ref "R101")
      (value "510")
      (footprint "eagle-import:X0805")
      (libsource (lib "eagle-import") (part "R-EU_X0805"))
    )
    (comp (ref "R102")
      (value "1k")
      (footprint "eagle-import:X0805")
      (libsource (lib "eagle-import") (part "R-EU_X0805"))
    )
    (comp (ref "R103")
      (value "11k")
      (footprint "eagle-import:X0805")
      (libsource (lib "eagle-import") (part "R-EU_X0805"))
    )
    (comp (ref "R104")
      (value "2R2")
      (footprint "eagle-import:X0805")
      (libsource (lib "eagle-import") (part "R-EU_X0805"))
    )
    (comp (ref "R105")
      (value "2R2")
      (footprint "eagle-import:X0805")
      (libsource (lib "eagle-import") (part "R-EU_X0805"))
    )
    (comp (ref "R106")
      (value "100k")
      (footprint "eagle-import:X0805")
      (libsource (lib "eagle-import") (part "R-EU_X0805"))
    )
    (comp (ref "R107")
      (value "5x33R")
      (footprint "eagle-import:X0805")
      (libsource (lib "eagle-import") (part "R-EU_X0805"))
    )
    (comp (ref "R108")
      (value "R-EU_X0805")
      (footprint "eagle-import:X0805")
      (libsource (lib "eagle-import") (part "R-EU_X0805"))
    )
    (comp (ref "R109")
      (value "1k")
      (footprint "eagle-import:X0805")
      (libsource (lib "eagle-import") (part "R-EU_X0805"))
    )
    (comp (ref "R110")
      (value "R-EU_X0805")
      (footprint "eagle-import:X0805")
      (libsource (lib "eagle-import") (part "R-EU_X0805"))
    )
    (comp (ref "R111")
      (value "2R2")
      (footprint "eagle-import:X0805")
      (libsource (lib "eagle-import") (part "R-EU_X0805"))
    )
    (comp (ref "R112")
      (value "2R2")
      (footprint "eagle-import:X0805")
      (libsource (lib "eagle-import") (part "R-EU_X0805"))
    )
    (comp (ref "R113")
      (value "1k")
      (footprint "eagle-import:X0805")
      (libsource (lib "eagle-import") (part "R0805"))
    )
    (comp (ref "R114")
      (value "R-EU_X0805")
      (footprint "eagle-import:X0805")
      (libsource (lib "eagle-import") (part "R-EU_X0805"))
    )
    (comp (ref "R115")
      (value "11k")
      (footprint "eagle-import:X0805")
      (libsource (lib "eagle-import") (part "R-EU_X0805"))
    )
    (comp (ref "R116")
      (value "R-EU_X0805")
      (footprint "eagle-import:X0805")
      (libsource (lib "eagle-import") (part "R-EU_X0805"))
    )
    (comp (ref "R117")
      (value "100k")
      (footprint "eagle-import:X0805")
      (libsource (lib "eagle-import") (part "R-EU_X0805"))
    )
    (comp (ref "R118")
      (value "R-EU_X0805")
      (footprint "eagle-import:X0805")
      (libsource (lib "eagle-import") (part "R-EU_X0805"))
    )
    (comp (ref "R119")
      (value "12k")
      (footprint "eagle-import:X0805")
      (libsource (lib "eagle-import") (part "R-EU_X0805"))
    )
    (comp (ref "R120")
      (value "R-EU_X0805")
      (footprint "eagle-import:X0805")
      (libsource (lib "eagle-import") (part "R-EU_X0805"))
    )
    (comp (ref "R121")
      (value "R-EU_X0805")
      (footprint "eagle-import:X0805")
      (libsource (lib "eagle-import") (part "R-EU_X0805"))
    )
    (comp (ref "R122")
      (value "R-EU_X0805")
      (footprint "eagle-import:X0805")
      (libsource (lib "eagle-import") (part "R-EU_X0805"))
    )
    (comp (ref "R123")
      (value "5x33R")
      (footprint "eagle-import:X0805")
      (libsource (lib "eagle-import") (part "R-EU_X0805"))
    )
    (comp (ref "R124")
      (value "2k2")
      (footprint "eagle-import:X0805")
      (libsource (lib "eagle-import") (part "R0805"))
    )
    (comp (ref "R125")
      (value "2k2")
      (footprint "eagle-import:X0805")
      (libsource (lib "eagle-import") (part "R0805"))
    )
    (comp (ref "R126")
      (value "430")
      (footprint "eagle-import:X0805")
      (libsource (lib "eagle-import") (part "R-EU_X0805"))
    )
    (comp (ref "R127")
      (value "10k")
      (footprint "eagle-import:X0805")
      (libsource (lib "eagle-import") (part "R0805"))
    )
    (comp (ref "R128")
      (value "2R2")
      (footprint "eagle-import:X0805")
      (libsource (lib "eagle-import") (part "R-EU_X0805"))
    )
    (comp (ref "R129")
      (value "1k")
      (footprint "eagle-import:X0805")
      (libsource (lib "eagle-import") (part "R-EU_X0805"))
    )
    (comp (ref "R130")
      (value "510")
      (footprint "eagle-import:X0805")
      (libsource (lib "eagle-import") (part "R-EU_X0805"))
    )
    (comp (ref "R131")
      (value "2R2")
      (footprint "eagle-import:X0805")
      (libsource (lib "eagle-import") (part "R-EU_X0805"))
    )
    (comp (ref "R132")
      (value "10k")
      (footprint "eagle-import:X0805")
      (libsource (lib "eagle-import") (part "R0805"))
    )
    (comp (ref "R133")
      (value "560")
      (footprint "eagle-import:X0805")
      (libsource (lib "eagle-import") (part "R0805"))
    )
    (comp (ref "R134")
      (value "2k2")
      (footprint "eagle-import:X0805")
      (libsource (lib "eagle-import") (part "R-EU_X0805"))
    )
    (comp (ref "R135")
      (value "2k2")
      (footprint "eagle-import:X0805")
      (libsource (lib "eagle-import") (part "R-EU_X0805"))
    )
    (comp (ref "R136")
      (value "560")
      (footprint "eagle-import:X0805")
      (libsource (lib "eagle-import") (part "R0805"))
    )
    (comp (ref "R137")
      (value "4k7")
      (footprint "eagle-import:X0805")
      (libsource (lib "eagle-import") (part "R-EU_X0805"))
    )
    (comp (ref "RN1")
      (value "4x50")
      (footprint "eagle-import:SIL5")
      (libsource (lib "eagle-import") (part "G04R"))
    )
    (comp (ref "RN2")
      (value "4x50")
      (footprint "eagle-import:SIL5")
      (libsource (lib "eagle-import") (part "G04R"))
    )
    (comp (ref "RN3")
      (value "4x50")
      (footprint "eagle-import:SIL5")
      (libsource (lib "eagle-import") (part "G04R"))
    )
    (comp (ref "RN4")
      (value "4x50")
      (footprint "eagle-import:SIL5")
      (libsource (lib "eagle-import") (part "G04R"))
    )
    (comp (ref "SV1")
      (value "CONTROLS")
      (footprint "eagle-import:ML10")
      (libsource (lib "eagle-import") (part "ML10"))
    )
    (comp (ref "SV100")
      (value "CONTROLS")
      (footprint "eagle-import:ML10")
      (libsource (lib "eagle-import") (part "ML10"))
    )
    (comp (ref "TL1")
      (value "CUDL1_A")
      (footprint "eagle-import:CUDL1")
      (libsource (lib "eagle-import") (part "CUDL1_A"))
    )
    (comp (ref "TL2")
      (value "CUDL1_A")
      (footprint "eagle-import:CUDL1")
      (libsource (lib "eagle-import") (part "CUDL1_A"))
    )
    (comp (ref "TL3")
      (value "CUDL1_A")
      (footprint "eagle-import:CUDL1")
      (libsource (lib "eagle-import") (part "CUDL1_A"))
    )
    (comp (ref "TL4")
      (value "CUDL1_A")
      (footprint "eagle-import:CUDL1")
      (libsource (lib "eagle-import") (part "CUDL1_A"))
    )
    (comp (ref "TL5")
      (value "CUDL1_A")
      (footprint "eagle-import:CUDL1")
      (libsource (lib "eagle-import") (part "CUDL1_A"))
    )
    (comp (ref "U1")
      (value "LTC2631")
      (footprint "eagle-import:SOT65P280X100-8N")
      (fields (field (name "MPN") "LTC2631AITS8-LZ12#PBF"))
      (libsource (lib "eagle-import") (part "LTC2631AITS8-LZ12PBF"))
    )
    (comp (ref "U100")
      (value "LTC2631")
      (footprint "eagle-import:SOT65P280X100-8N")
      (fields (field (name "MPN") "LTC2631AITS8-LZ12#PBF"))
      (libsource (lib "eagle-import") (part "LTC2631AITS8-LZ12PBF"))
    )
    (comp (ref "X1")
      (value "PN61729-S")
      (footprint "eagle-import:PN61729-S")
      (libsource (lib "eagle-import") (part "PN61729-S"))
    )
    (comp (ref "X2")
      (value "Bcur")
      (footprint "eagle-import:A1944")
      (libsource (lib "eagle-import") (part "A1944-50"))
    )
    (comp (ref "X3")
      (value "Bcur")
      (footprint "eagle-import:A1944")
      (libsource (lib "eagle-import") (part "A1944-50"))
    )
    (comp (ref "X4")
      (value "Lcur")
      (footprint "eagle-import:A1944")
      (libsource (lib "eagle-import") (part "A1944-50"))
    )
    (comp (ref "X5")
      (value "Hcur")
      (footprint "eagle-import:A1944")
      (libsource (lib "eagle-import") (part "A1944-50"))
    )
    (comp (ref "X6")
      (value "Lpot")
      (footprint "eagle-import:A1944")
      (libsource (lib "eagle-import") (part "A1944-50"))
    )
    (comp (ref "X7")
      (value "Hpot")
      (footprint "eagle-import:A1944")
      (libsource (lib "eagle-import") (part "A1944-50"))
    )
    (comp (ref "X8")
      (value "Bpot")
      (footprint "eagle-import:A1944")
      (libsource (lib "eagle-import") (part "A1944-50"))
    )
    (comp (ref "X9")
      (value "Bpot")
      (footprint "eagle-import:A1944")
      (libsource (lib "eagle-import") (part "A1944-50"))
    )
  )
  (nets
    (net (code "1") (name "+5V") (class "Default")
      (node (ref "C100") (pin "P$1") (pinfunction "1_P$1") (pintype "passive"))
      (node (ref "C107") (pin "P$1") (pinfunction "1_P$1") (pintype "passive"))
      (node (ref "C109") (pin "P$1") (pinfunction "1_P$1") (pintype "passive"))
      (node (ref "C110") (pin "1") (pinfunction "1_1") (pintype "passive"))
      (node (ref "C120") (pin "1") (pinfunction "1_1") (pintype "passive"))
      (node (ref "C123") (pin "P$1") (pinfunction "1_P$1") (pintype "passive"))
      (node (ref "C140") (pin "P$1") (pinfunction "1_P$1") (pintype "passive"))
      (node (ref "C143") (pin "P$1") (pinfunction "1_P$1") (pintype "passive"))
      (node (ref "C24") (pin "+") (pinfunction "+_+") (pintype "passive"))
      (node (ref "IC100") (pin "1") (pinfunction "VDD1_1") (pintype "power_in"))
      (node (ref "IC104") (pin "1") (pinfunction "VDD1_1") (pintype "power_in"))
      (node (ref "IC105") (pin "3") (pinfunction "VDDA_3") (pintype "power_in"))
      (node (ref "IC3") (pin "20") (pinfunction "AVCC_20") (pintype "power_in"))
      (node (ref "IC3") (pin "7") (pinfunction "VCC_7") (pintype "power_in"))
      (node (ref "IC5") (pin "1") (pinfunction "VCC_1") (pintype "power_in"))
      (node (ref "IC5") (pin "15") (pinfunction "COM_15") (pintype "bidirectional"))
      (node (ref "IC5") (pin "2") (pinfunction "SET_2") (pintype "input"))
      (node (ref "K19") (pin "6") (pinfunction "6_6") (pintype "passive"))
      (node (ref "K24") (pin "4") (pinfunction "4_4") (pintype "passive"))
      (node (ref "K25") (pin "6") (pinfunction "6_6") (pintype "passive"))
      (node (ref "L100") (pin "2") (pinfunction "2_2") (pintype "passive"))
      (node (ref "M+5V") (pin "1") (pinfunction "P$1_1") (pintype "passive"))
      (node (ref "R100") (pin "P$2") (pinfunction "2_P$2") (pintype "passive"))
      (node (ref "R113") (pin "P$2") (pinfunction "2_P$2") (pintype "passive"))
      (node (ref "R124") (pin "P$2") (pinfunction "2_P$2") (pintype "passive"))
      (node (ref "R125") (pin "P$2") (pinfunction "2_P$2") (pintype "passive"))
      (node (ref "R126") (pin "P$2") (pinfunction "2_P$2") (pintype "passive"))
      (node (ref "R25") (pin "P$2") (pinfunction "2_P$2") (pintype "passive"))
      (node (ref "R6") (pin "P$2") (pinfunction "2_P$2") (pintype "passive"))
      (node (ref "RN1") (pin "1") (pinfunction "1_1") (pintype "passive"))
      (node (ref "RN2") (pin "1") (pinfunction "1_1") (pintype "passive"))
      (node (ref "RN3") (pin "1") (pinfunction "1_1") (pintype "passive"))
      (node (ref "RN4") (pin "1") (pinfunction "1_1") (pintype "passive"))
    )
    (net (code "2") (name "+5V{slash}1") (class "Default")
      (node (ref "C27") (pin "P$2") (pinfunction "2_P$2") (pintype "passive"))
      (node (ref "C28") (pin "+") (pinfunction "+_+") (pintype "passive"))
      (node (ref "IC100") (pin "8") (pinfunction "VDD2_8") (pintype "power_in"))
      (node (ref "IC101") (pin "5") (pinfunction "OUT_5") (pintype "power_in"))
      (node (ref "P+5V") (pin "1") (pinfunction "P$1_1") (pintype "passive"))
      (node (ref "R28") (pin "P$2") (pinfunction "2_P$2") (pintype "passive"))
      (node (ref "R29") (pin "P$2") (pinfunction "2_P$2") (pintype "passive"))
      (node (ref "U1") (pin "1") (pinfunction "CA0_1") (pintype "input"))
      (node (ref "U1") (pin "5") (pinfunction "VCC_5") (pintype "power_in"))
      (node (ref "U1") (pin "8") (pinfunction "CA1_8") (pintype "input"))
    )
    (net (code "3") (name "+5V{slash}2") (class "Default")
      (node (ref "C+5V") (pin "1") (pinfunction "P$1_1") (pintype "passive"))
      (node (ref "C141") (pin "P$1") (pinfunction "1_P$1") (pintype "passive"))
      (node (ref "C142") (pin "1") (pinfunction "1_1") (pintype "passive"))
      (node (ref "C146") (pin "P$2") (pinfunction "2_P$2") (pintype "passive"))
      (node (ref "IC104") (pin "8") (pinfunction "VDD2_8") (pintype "power_in"))
      (node (ref "IC106") (pin "5") (pinfunction "OUT_5") (pintype "power_in"))
      (node (ref "R134") (pin "P$2") (pinfunction "2_P$2") (pintype "passive"))
      (node (ref "R135") (pin "P$2") (pinfunction "2_P$2") (pintype "passive"))
      (node (ref "R20") (pin "1") (pinfunction "E_1") (pintype "passive"))
      (node (ref "U100") (pin "5") (pinfunction "VCC_5") (pintype "power_in"))
    )
    (net (code "4") (name "+9V") (class "Default")
      (node (ref "C+9V") (pin "1") (pinfunction "P$1_1") (pintype "passive"))
      (node (ref "C13") (pin "+") (pinfunction "+_+") (pintype "passive"))
      (node (ref "C131") (pin "1") (pinfunction "1_1") (pintype "passive"))
      (node (ref "C132") (pin "P$2") (pinfunction "2_P$2") (pintype "passive"))
      (node (ref "C14") (pin "+") (pinfunction "+_+") (pintype "passive"))
      (node (ref "C148") (pin "P$2") (pinfunction "2_P$2") (pintype "passive"))
      (node (ref "C154") (pin "1") (pinfunction "1_1") (pintype "passive"))
      (node (ref "C2") (pin "+") (pinfunction "+_+") (pintype "passive"))
      (node (ref "IC106") (pin "1") (pinfunction "IN_1") (pintype "power_in"))
      (node (ref "IC106") (pin "3") (pinfunction "ON/OFF_3") (pintype "bidirectional"))
      (node (ref "IC2") (pin "5") (pinfunction "V+_5") (pintype "power_in"))
      (node (ref "IC2") (pin "7") (pinfunction "E/S_7") (pintype "bidirectional"))
      (node (ref "L2") (pin "2") (pinfunction "2_2") (pintype "passive"))
      (node (ref "R3") (pin "P$2") (pinfunction "2_P$2") (pintype "passive"))
    )
    (net (code "5") (name "+10V") (class "Default")
      (node (ref "C102") (pin "P$2") (pinfunction "2_P$2") (pintype "passive"))
      (node (ref "C112") (pin "P$1") (pinfunction "1_P$1") (pintype "passive"))
      (node (ref "C116") (pin "P$1") (pinfunction "1_P$1") (pintype "passive"))
      (node (ref "C18") (pin "+") (pinfunction "+_+") (pintype "passive"))
      (node (ref "D6") (pin "C") (pinfunction "C_C") (pintype "passive"))
      (node (ref "IC101") (pin "1") (pinfunction "IN_1") (pintype "power_in"))
      (node (ref "IC101") (pin "3") (pinfunction "ON/OFF_3") (pintype "bidirectional"))
      (node (ref "IC102") (pin "5") (pinfunction "VOUT_5") (pintype "passive"))
      (node (ref "IC4") (pin "7") (pinfunction "V+_7") (pintype "power_in"))
      (node (ref "P+10V") (pin "1") (pinfunction "P$1_1") (pintype "passive"))
      (node (ref "R106") (pin "P$2") (pinfunction "2_P$2") (pintype "passive"))
      (node (ref "R109") (pin "P$1") (pinfunction "1_P$1") (pintype "passive"))
      (node (ref "R21") (pin "P$2") (pinfunction "2_P$2") (pintype "passive"))
      (node (ref "R24") (pin "1") (pinfunction "E_1") (pintype "passive"))
    )
    (net (code "6") (name "-3V3") (class "Default")
      (node (ref "C-3V3") (pin "1") (pinfunction "P$1_1") (pintype "passive"))
      (node (ref "C10") (pin "P$2") (pinfunction "2_P$2") (pintype "passive"))
      (node (ref "C137") (pin "P$1") (pinfunction "1_P$1") (pintype "passive"))
      (node (ref "C138") (pin "2") (pinfunction "2_2") (pintype "passive"))
      (node (ref "C4") (pin "-") (pinfunction "-_-") (pintype "passive"))
      (node (ref "C7") (pin "-") (pinfunction "-_-") (pintype "passive"))
      (node (ref "IC2") (pin "4") (pinfunction "V-_4") (pintype "power_in"))
      (node (ref "L4") (pin "2") (pinfunction "2_2") (pintype "passive"))
      (node (ref "R11") (pin "P$2") (pinfunction "2_P$2") (pintype "passive"))
      (node (ref "R13") (pin "P$1") (pinfunction "1_P$1") (pintype "passive"))
      (node (ref "R5") (pin "P$2") (pinfunction "2_P$2") (pintype "passive"))
    )
    (net (code "7") (name "-10V") (class "Default")
      (node (ref "C118") (pin "P$2") (pinfunction "2_P$2") (pintype "passive"))
      (node (ref "C122") (pin "P$2") (pinfunction "2_P$2") (pintype "passive"))
      (node (ref "C19") (pin "-") (pinfunction "-_-") (pintype "passive"))
      (node (ref "D7") (pin "A") (pinfunction "A_A") (pintype "passive"))
      (node (ref "IC103") (pin "5") (pinfunction "VOUT_5") (pintype "passive"))
      (node (ref "IC4") (pin "4") (pinfunction "V-_4") (pintype "power_in"))
      (node (ref "P-10V") (pin "1") (pinfunction "P$1_1") (pintype "passive"))
      (node (ref "R117") (pin "P$1") (pinfunction "1_P$1") (pintype "passive"))
      (node (ref "R119") (pin "P$2") (pinfunction "2_P$2") (pintype "passive"))
      (node (ref "R22") (pin "P$2") (pinfunction "2_P$2") (pintype "passive"))
      (node (ref "R24") (pin "3") (pinfunction "A_3") (pintype "passive"))
    )
    (net (code "8") (name "/B0") (class "Default")
      (node (ref "IC3") (pin "13") (pinfunction "PD7(PCINT23/AIN1)_13") (pintype "bidirectional"))
      (node (ref "R108") (pin "P$2") (pinfunction "2_P$2") (pintype "passive"))
    )
    (net (code "9") (name "/B1") (class "Default")
      (node (ref "IC3") (pin "12") (pinfunction "PD6(PCINT22/OC0A/AIN0)_12") (pintype "bidirectional"))
      (node (ref "R107") (pin "P$1") (pinfunction "1_P$1") (pintype "passive"))
    )
    (net (code "10") (name "/D0") (class "Default")
      (node (ref "IC3") (pin "25") (pinfunction "PC2(ADC2/PCINT10)_25") (pintype "bidirectional"))
      (node (ref "R123") (pin "P$2") (pinfunction "2_P$2") (pintype "passive"))
    )
    (net (code "11") (name "/D1") (class "Default")
      (node (ref "IC3") (pin "5") (pinfunction "PD3(PCINT19/OC2B/INT1)_5") (pintype "bidirectional"))
      (node (ref "R122") (pin "P$1") (pinfunction "1_P$1") (pintype "passive"))
    )
    (net (code "12") (name "/D2") (class "Default")
      (node (ref "IC3") (pin "24") (pinfunction "PC1(ADC1/PCINT9)_24") (pintype "bidirectional"))
      (node (ref "R121") (pin "P$2") (pinfunction "2_P$2") (pintype "passive"))
    )
    (net (code "13") (name "/D3") (class "Default")
      (node (ref "IC3") (pin "6") (pinfunction "PD4(PCINT20/XCK/T0)_6") (pintype "bidirectional"))
      (node (ref "R120") (pin "P$1") (pinfunction "1_P$1") (pintype "passive"))
    )
    (net (code "14") (name "/D4") (class "Default")
      (node (ref "IC3") (pin "23") (pinfunction "PC0(ADC0/PCINT8)_23") (pintype "bidirectional"))
      (node (ref "R118") (pin "P$2") (pinfunction "2_P$2") (pintype "passive"))
    )
    (net (code "15") (name "/GPIO0") (class "Default")
      (node (ref "IC3") (pin "14") (pinfunction "PB0(PCINT0/CLKO/ICP1)_14") (pintype "bidirectional"))
      (node (ref "K24") (pin "2") (pinfunction "2_2") (pintype "passive"))
    )
    (net (code "16") (name "/GPIO1") (class "Default")
      (node (ref "IC3") (pin "15") (pinfunction "PB1(OC1A/PCINT1)_15") (pintype "bidirectional"))
      (node (ref "K24") (pin "3") (pinfunction "3_3") (pintype "passive"))
    )
    (net (code "17") (name "/L0") (class "Default")
      (node (ref "IC3") (pin "9") (pinfunction "PB6(PCINT6/XTAL1/TOSC1)_9") (pintype "bidirectional"))
      (node (ref "R116") (pin "P$1") (pinfunction "1_P$1") (pintype "passive"))
    )
    (net (code "18") (name "/L1") (class "Default")
      (node (ref "IC3") (pin "11") (pinfunction "PD5(PCINT21/OC0B/T1)_11") (pintype "bidirectional"))
      (node (ref "R110") (pin "P$2") (pinfunction "2_P$2") (pintype "passive"))
    )
    (net (code "19") (name "/L2") (class "Default")
      (node (ref "IC3") (pin "10") (pinfunction "PB7(PCINT7/XTAL2/TOSC2)_10") (pintype "bidirectional"))
      (node (ref "R114") (pin "P$1") (pinfunction "1_P$1") (pintype "passive"))
    )
    (net (code "20") (name "/MISO") (class "Default")
      (node (ref "IC3") (pin "18") (pinfunction "PB4(MISO/PCINT4)_18") (pintype "bidirectional"))
      (node (ref "K19") (pin "3") (pinfunction "3_3") (pintype "passive"))
      (node (ref "K25") (pin "4") (pinfunction "4_4") (pintype "passive"))
    )
    (net (code "21") (name "/MOSI") (class "Default")
      (node (ref "IC3") (pin "17") (pinfunction "PB3(MOSI/OC2A/PCINT3)_17") (pintype "bidirectional"))
      (node (ref "IC5") (pin "5") (pinfunction "DIN_5") (pintype "input"))
      (node (ref "K19") (pin "2") (pinfunction "2_2") (pintype "passive"))
      (node (ref "K25") (pin "3") (pinfunction "3_3") (pintype "passive"))
    )
    (net (code "22") (name "/RST") (class "Default")
      (node (ref "IC3") (pin "1") (pinfunction "PC6(PCINT14/RESET)_1") (pintype "bidirectional"))
      (node (ref "K19") (pin "5") (pinfunction "5_5") (pintype "passive"))
      (node (ref "R113") (pin "P$1") (pinfunction "1_P$1") (pintype "passive"))
    )
    (net (code "23") (name "/SCK") (class "Default")
      (node (ref "IC3") (pin "19") (pinfunction "PB5(SCK/PCINT5)_19") (pintype "bidirectional"))
      (node (ref "IC5") (pin "6") (pinfunction "CLK_6") (pintype "input"))
      (node (ref "K19") (pin "4") (pinfunction "4_4") (pintype "passive"))
      (node (ref "K25") (pin "5") (pinfunction "5_5") (pintype "passive"))
    )
    (net (code "24") (name "/SS") (class "Default")
      (node (ref "IC3") (pin "16") (pinfunction "PB2(SS/OC1B/PCINT2)_16") (pintype "bidirectional"))
      (node (ref "IC5") (pin "4") (pinfunction "CS_4") (pintype "input"))
      (node (ref "K25") (pin "2") (pinfunction "2_2") (pintype "passive"))
    )
    (net (code "25") (name "FAN") (class "Default")
      (node (ref "IC3") (pin "26") (pinfunction "PC3(ADC3/PCINT11)_26") (pintype "bidirectional"))
      (node (ref "R127") (pin "P$1") (pinfunction "1_P$1") (pintype "passive"))
      (node (ref "R132") (pin "P$1") (pinfunction "1_P$1") (pintype "passive"))
    )
    (net (code "26") (name "GND") (class "Default")
      (node (ref "C1") (pin "-") (pinfunction "-_-") (pintype "passive"))
      (node (ref "C100") (pin "P$2") (pinfunction "2_P$2") (pintype "passive"))
      (node (ref "C101") (pin "P$2") (pinfunction "2_P$2") (pintype "passive"))
      (node (ref "C105") (pin "2") (pinfunction "2_2") (pintype "passive"))
      (node (ref "C106") (pin "P$2") (pinfunction "2_P$2") (pintype "passive"))
      (node (ref "C107") (pin "P$2") (pinfunction "2_P$2") (pintype "passive"))
      (node (ref "C109") (pin "P$2") (pinfunction "2_P$2") (pintype "passive"))
      (node (ref "C110") (pin "2") (pinfunction "2_2") (pintype "passive"))
      (node (ref "C115") (pin "P$2") (pinfunction "2_P$2") (pintype "passive"))
      (node (ref "C117") (pin "2") (pinfunction "2_2") (pintype "passive"))
      (node (ref "C120") (pin "2") (pinfunction "2_2") (pintype "passive"))
      (node (ref "C121") (pin "P$2") (pinfunction "2_P$2") (pintype "passive"))
      (node (ref "C123") (pin "P$2") (pinfunction "2_P$2") (pintype "passive"))
      (node (ref "C124") (pin "P$2") (pinfunction "2_P$2") (pintype "passive"))
      (node (ref "C125") (pin "2") (pinfunction "2_2") (pintype "passive"))
      (node (ref "C133") (pin "2") (pinfunction "2_2") (pintype "passive"))
      (node (ref "C140") (pin "P$2") (pinfunction "2_P$2") (pintype "passive"))
      (node (ref "C143") (pin "P$2") (pinfunction "2_P$2") (pintype "passive"))
      (node (ref "C144") (pin "2") (pinfunction "2_2") (pintype "passive"))
      (node (ref "C15") (pin "2") (pinfunction "2_2") (pintype "passive"))
      (node (ref "C16") (pin "P$2") (pinfunction "2_P$2") (pintype "passive"))
      (node (ref "C17") (pin "2") (pinfunction "2_2") (pintype "passive"))
      (node (ref "C24") (pin "-") (pinfunction "-_-") (pintype "passive"))
      (node (ref "D3") (pin "A") (pinfunction "A_A") (pintype "passive"))
      (node (ref "D5") (pin "A") (pinfunction "A_A") (pintype "passive"))
      (node (ref "IC100") (pin "4") (pinfunction "GND1_4") (pintype "power_in"))
      (node (ref "IC104") (pin "4") (pinfunction "GND1_4") (pintype "power_in"))
      (node (ref "IC105") (pin "1") (pinfunction "GNDA_1") (pintype "power_in"))
      (node (ref "IC3") (pin "22") (pinfunction "GND_22") (pintype "power_in"))
      (node (ref "IC3") (pin "8") (pinfunction "GND_8") (pintype "power_in"))
      (node (ref "IC5") (pin "0") (pinfunction "GND_0") (pintype "power_in"))
      (node (ref "IC5") (pin "12") (pinfunction "PGND_12") (pintype "bidirectional"))
      (node (ref "IC5") (pin "18") (pinfunction "PGND_18") (pintype "bidirectional"))
      (node (ref "IC5") (pin "9") (pinfunction "GND_9") (pintype "power_in"))
      (node (ref "K1") (pin "1") (pinfunction "1_1") (pintype "passive"))
      (node (ref "K19") (pin "1") (pinfunction "1_1") (pintype "passive"))
      (node (ref "K2") (pin "1") (pinfunction "1_1") (pintype "passive"))
      (node (ref "K24") (pin "1") (pinfunction "1_1") (pintype "passive"))
      (node (ref "K25") (pin "1") (pinfunction "1_1") (pintype "passive"))
      (node (ref "L3") (pin "3") (pinfunction "3_3") (pintype "passive"))
      (node (ref "L5") (pin "3") (pinfunction "3_3") (pintype "passive"))
      (node (ref "LED17") (pin "C") (pinfunction "C_C") (pintype "passive"))
      (node (ref "MGND") (pin "1") (pinfunction "P$1_1") (pintype "passive"))
      (node (ref "OK101") (pin "2") (pinfunction "C_2") (pintype "passive"))
      (node (ref "PSU3") (pin "2") (pinfunction "-VIN_2") (pintype "passive"))
      (node (ref "PSU3") (pin "3") (pinfunction "-VIN1_3") (pintype "passive"))
      (node (ref "PSU4") (pin "2") (pinfunction "GND_2") (pintype "passive"))
      (node (ref "Q100") (pin "E") (pinfunction "E_E") (pintype "passive"))
      (node (ref "Q101") (pin "E") (pinfunction "E_E") (pintype "passive"))
    )
    (net (code "27") (name "GND1") (class "Default")
      (node (ref "C102") (pin "P$1") (pinfunction "1_P$1") (pintype "passive"))
      (node (ref "C103") (pin "2") (pinfunction "2_2") (pintype "passive"))
      (node (ref "C104") (pin "P$2") (pinfunction "2_P$2") (pintype "passive"))
      (node (ref "C108") (pin "P$2") (pinfunction "2_P$2") (pintype "passive"))
      (node (ref "C111") (pin "2") (pinfunction "2_2") (pintype "passive"))
      (node (ref "C112") (pin "P$2") (pinfunction "2_P$2") (pintype "passive"))
      (node (ref "C113") (pin "2") (pinfunction "2_2") (pintype "passive"))
      (node (ref "C114") (pin "P$2") (pinfunction "2_P$2") (pintype "passive"))
      (node (ref "C116") (pin "P$2") (pinfunction "2_P$2") (pintype "passive"))
      (node (ref "C118") (pin "P$1") (pinfunction "1_P$1") (pintype "passive"))
      (node (ref "C122") (pin "P$1") (pinfunction "1_P$1") (pintype "passive"))
      (node (ref "C126") (pin "P$1") (pinfunction "1_P$1") (pintype "passive"))
      (node (ref "C127") (pin "1") (pinfunction "1_1") (pintype "passive"))
      (node (ref "C129") (pin "1") (pinfunction "1_1") (pintype "passive"))
      (node (ref "C130") (pin "P$1") (pinfunction "1_P$1") (pintype "passive"))
      (node (ref "C18") (pin "-") (pinfunction "-_-") (pintype "passive"))
      (node (ref "C19") (pin "+") (pinfunction "+_+") (pintype "passive"))
      (node (ref "C20") (pin "-") (pinfunction "-_-") (pintype "passive"))
      (node (ref "C21") (pin "-") (pinfunction "-_-") (pintype "passive"))
      (node (ref "C23") (pin "-") (pinfunction "-_-") (pintype "passive"))
      (node (ref "C25") (pin "-") (pinfunction "-_-") (pintype "passive"))
      (node (ref "C26") (pin "P$2") (pinfunction "2_P$2") (pintype "passive"))
      (node (ref "C27") (pin "P$1") (pinfunction "1_P$1") (pintype "passive"))
      (node (ref "C28") (pin "-") (pinfunction "-_-") (pintype "passive"))
      (node (ref "D6") (pin "A") (pinfunction "A_A") (pintype "passive"))
      (node (ref "D7") (pin "C") (pinfunction "C_C") (pintype "passive"))
      (node (ref "IC100") (pin "5") (pinfunction "GND2_5") (pintype "power_in"))
      (node (ref "IC101") (pin "2") (pinfunction "GND_2") (pintype "power_in"))
      (node (ref "IC102") (pin "2") (pinfunction "GND_2") (pintype "power_in"))
      (node (ref "IC103") (pin "1") (pinfunction "GND_1") (pintype "power_in"))
      (node (ref "LED15") (pin "C") (pinfunction "C_C") (pintype "passive"))
      (node (ref "LED16") (pin "A") (pinfunction "A_A") (pintype "passive"))
      (node (ref "PGND") (pin "1") (pinfunction "P$1_1") (pintype "passive"))
      (node (ref "PSU3") (pin "16") (pinfunction "COM_16") (pintype "passive"))
      (node (ref "PSU3") (pin "9") (pinfunction "COM_9") (pintype "passive"))
      (node (ref "R103") (pin "P$1") (pinfunction "1_P$1") (pintype "passive"))
      (node (ref "R115") (pin "P$2") (pinfunction "2_P$2") (pintype "passive"))
      (node (ref "R30") (pin "2") (pinfunction "S_2") (pintype "passive"))
      (node (ref "R30") (pin "3") (pinfunction "A_3") (pintype "passive"))
      (node (ref "U1") (pin "4") (pinfunction "GND_4") (pintype "passive"))
      (node (ref "X9") (pin "1") (pinfunction "1_1") (pintype "passive"))
    )
    (net (code "28") (name "GND2") (class "Default")
      (node (ref "C11") (pin "-") (pinfunction "-_-") (pintype "passive"))
      (node (ref "C13") (pin "-") (pinfunction "-_-") (pintype "passive"))
      (node (ref "C131") (pin "2") (pinfunction "2_2") (pintype "passive"))
      (node (ref "C132") (pin "P$1") (pinfunction "1_P$1") (pintype "passive"))
      (node (ref "C135") (pin "2") (pinfunction "2_2") (pintype "passive"))
      (node (ref "C137") (pin "P$2") (pinfunction "2_P$2") (pintype "passive"))
      (node (ref "C138") (pin "1") (pinfunction "1_1") (pintype "passive"))
      (node (ref "C14") (pin "-") (pinfunction "-_-") (pintype "passive"))
      (node (ref "C141") (pin "P$2") (pinfunction "2_P$2") (pintype "passive"))
      (node (ref "C142") (pin "2") (pinfunction "2_2") (pintype "passive"))
      (node (ref "C145") (pin "1") (pinfunction "1_1") (pintype "passive"))
      (node (ref "C146") (pin "P$1") (pinfunction "1_P$1") (pintype "passive"))
      (node (ref "C147") (pin "P$2") (pinfunction "2_P$2") (pintype "passive"))
      (node (ref "C148") (pin "P$1") (pinfunction "1_P$1") (pintype "passive"))
      (node (ref "C154") (pin "2") (pinfunction "2_2") (pintype "passive"))
      (node (ref "C155") (pin "2") (pinfunction "2_2") (pintype "passive"))
      (node (ref "C2") (pin "-") (pinfunction "-_-") (pintype "passive"))
      (node (ref "C3") (pin "-") (pinfunction "-_-") (pintype "passive"))
      (node (ref "C4") (pin "+") (pinfunction "+_+") (pintype "passive"))
      (node (ref "C5") (pin "-") (pinfunction "-_-") (pintype "passive"))
      (node (ref "C6") (pin "P$2") (pinfunction "2_P$2") (pintype "passive"))
      (node (ref "C7") (pin "+") (pinfunction "+_+") (pintype "passive"))
      (node (ref "C8") (pin "-") (pinfunction "-_-") (pintype "passive"))
      (node (ref "CGND") (pin "1") (pinfunction "P$1_1") (pintype "passive"))
      (node (ref "D100") (pin "C") (pinfunction "C_C") (pintype "passive"))
      (node (ref "IC104") (pin "5") (pinfunction "GND2_5") (pintype "power_in"))
      (node (ref "IC106") (pin "2") (pinfunction "GND_2") (pintype "power_in"))
      (node (ref "K101") (pin "4") (pinfunction "S_4") (pintype "passive"))
      (node (ref "K101") (pin "5") (pinfunction "S_5") (pintype "passive"))
      (node (ref "K102") (pin "2") (pinfunction "O_2") (pintype "passive"))
      (node (ref "K102") (pin "7") (pinfunction "O_7") (pintype "passive"))
      (node (ref "LED3") (pin "C") (pinfunction "C_C") (pintype "passive"))
      (node (ref "LED4") (pin "A") (pinfunction "A_A") (pintype "passive"))
      (node (ref "PSU1") (pin "5") (pinfunction "VOUT-_5") (pintype "power_in"))
      (node (ref "PSU2") (pin "4") (pinfunction "VOUT+_4") (pintype "power_in"))
      (node (ref "R18") (pin "1") (pinfunction "1_1") (pintype "passive"))
      (node (ref "R7") (pin "2") (pinfunction "S_2") (pintype "passive"))
      (node (ref "R7") (pin "3") (pinfunction "A_3") (pintype "passive"))
      (node (ref "U100") (pin "1") (pinfunction "CA0_1") (pintype "input"))
      (node (ref "U100") (pin "4") (pinfunction "GND_4") (pintype "passive"))
      (node (ref "U100") (pin "8") (pinfunction "CA1_8") (pintype "input"))
      (node (ref "X2") (pin "1") (pinfunction "1_1") (pintype "passive"))
    )
    (net (code "29") (name "Net-(C-HI-PadP$1)") (class "Default")
      (node (ref "C-HI") (pin "P$1") (pinfunction "P$1_P$1") (pintype "passive"))
      (node (ref "X3") (pin "1") (pinfunction "1_1") (pintype "passive"))
    )
    (net (code "30") (name "Net-(C6-1)") (class "Default")
      (node (ref "C6") (pin "P$1") (pinfunction "1_P$1") (pintype "passive"))
      (node (ref "U100") (pin "6") (pinfunction "REF_6") (pintype "bidirectional"))
    )
    (net (code "31") (name "Net-(C10-1)") (class "Default")
      (node (ref "C10") (pin "P$1") (pinfunction "1_P$1") (pintype "passive"))
      (node (ref "IC2") (pin "3") (pinfunction "ILIM_3") (pintype "input"))
      (node (ref "R11") (pin "P$1") (pinfunction "1_P$1") (pintype "passive"))
    )
    (net (code "32") (name "Net-(C12-Pad2)") (class "Default")
      (node (ref "C12") (pin "2") (pinfunction "2_2") (pintype "passive"))
      (node (ref "R18") (pin "2") (pinfunction "2_2") (pintype "passive"))
    )
    (net (code "33") (name "Net-(C20-Pad+)") (class "Default")
      (node (ref "C20") (pin "+") (pinfunction "+_+") (pintype "passive"))
      (node (ref "C21") (pin "+") (pinfunction "+_+") (pintype "passive"))
      (node (ref "C23") (pin "+") (pinfunction "+_+") (pintype "passive"))
      (node (ref "C25") (pin "+") (pinfunction "+_+") (pintype "passive"))
      (node (ref "R23") (pin "2") (pinfunction "2_2") (pintype "passive"))
      (node (ref "R26") (pin "2") (pinfunction "2_2") (pintype "passive"))
      (node (ref "X7") (pin "1") (pinfunction "1_1") (pintype "passive"))
    )
    (net (code "34") (name "Net-(C26-1)") (class "Default")
      (node (ref "C26") (pin "P$1") (pinfunction "1_P$1") (pintype "passive"))
      (node (ref "IC101") (pin "4") (pinfunction "BYPASS_4") (pintype "passive"))
    )
    (net (code "35") (name "Net-(C101-1)") (class "Default")
      (node (ref "C101") (pin "P$1") (pinfunction "1_P$1") (pintype "passive"))
      (node (ref "IC5") (pin "3") (pinfunction "RESET_3") (pintype "input"))
      (node (ref "R100") (pin "P$1") (pinfunction "1_P$1") (pintype "passive"))
    )
    (net (code "36") (name "Net-(C104-1)") (class "Default")
      (node (ref "C104") (pin "P$1") (pinfunction "1_P$1") (pintype "passive"))
      (node (ref "U1") (pin "6") (pinfunction "REF_6") (pintype "bidirectional"))
    )
    (net (code "37") (name "Net-(C106-1)") (class "Default")
      (node (ref "C105") (pin "1") (pinfunction "1_1") (pintype "passive"))
      (node (ref "C106") (pin "P$1") (pinfunction "1_P$1") (pintype "passive"))
      (node (ref "PSU3") (pin "22") (pinfunction "+VIN_22") (pintype "passive"))
      (node (ref "PSU3") (pin "23") (pinfunction "+VIN1_23") (pintype "passive"))
      (node (ref "R104") (pin "P$2") (pinfunction "2_P$2") (pintype "passive"))
      (node (ref "R105") (pin "P$2") (pinfunction "2_P$2") (pintype "passive"))
    )
    (net (code "38") (name "Net-(C108-1)") (class "Default")
      (node (ref "C108") (pin "P$1") (pinfunction "1_P$1") (pintype "passive"))
      (node (ref "C113") (pin "1") (pinfunction "1_1") (pintype "passive"))
      (node (ref "L101") (pin "1") (pinfunction "1_1") (pintype "passive"))
      (node (ref "PSU3") (pin "14") (pinfunction "+VOUT_14") (pintype "passive"))
    )
    (net (code "39") (name "Net-(C114-1)") (class "Default")
      (node (ref "C111") (pin "1") (pinfunction "1_1") (pintype "passive"))
      (node (ref "C114") (pin "P$1") (pinfunction "1_P$1") (pintype "passive"))
      (node (ref "IC102") (pin "1") (pinfunction "VIN_1") (pintype "power_in"))
      (node (ref "IC102") (pin "3") (pinfunction "EN_3") (pintype "input"))
      (node (ref "L101") (pin "2") (pinfunction "2_2") (pintype "passive"))
    )
    (net (code "40") (name "Net-(C115-1)") (class "Default")
      (node (ref "C115") (pin "P$1") (pinfunction "1_P$1") (pintype "passive"))
      (node (ref "C117") (pin "1") (pinfunction "1_1") (pintype "passive"))
      (node (ref "PSU4") (pin "1") (pinfunction "VIN_1") (pintype "passive"))
      (node (ref "R111") (pin "P$2") (pinfunction "2_P$2") (pintype "passive"))
      (node (ref "R112") (pin "P$2") (pinfunction "2_P$2") (pintype "passive"))
    )
    (net (code "41") (name "Net-(C119-1)") (class "Default")
      (node (ref "C119") (pin "P$1") (pinfunction "1_P$1") (pintype "passive"))
      (node (ref "R109") (pin "P$2") (pinfunction "2_P$2") (pintype "passive"))
    )
    (net (code "42") (name "Net-(C119-2)") (class "Default")
      (node (ref "C119") (pin "P$2") (pinfunction "2_P$2") (pintype "passive"))
      (node (ref "IC102") (pin "4") (pinfunction "ADJ_4") (pintype "input"))
      (node (ref "R103") (pin "P$2") (pinfunction "2_P$2") (pintype "passive"))
      (node (ref "R106") (pin "P$1") (pinfunction "1_P$1") (pintype "passive"))
    )
    (net (code "43") (name "Net-(C121-1)") (class "Default")
      (node (ref "C121") (pin "P$1") (pinfunction "1_P$1") (pintype "passive"))
      (node (ref "C17") (pin "1") (pinfunction "1_1") (pintype "passive"))
      (node (ref "L100") (pin "1") (pinfunction "1_1") (pintype "passive"))
      (node (ref "PSU4") (pin "3") (pinfunction "VOUT_3") (pintype "passive"))
    )
    (net (code "44") (name "Net-(C124-1)") (class "Default")
      (node (ref "C1") (pin "+") (pinfunction "+_+") (pintype "passive"))
      (node (ref "C124") (pin "P$1") (pinfunction "1_P$1") (pintype "passive"))
      (node (ref "C125") (pin "1") (pinfunction "1_1") (pintype "passive"))
      (node (ref "C133") (pin "1") (pinfunction "1_1") (pintype "passive"))
      (node (ref "C144") (pin "1") (pinfunction "1_1") (pintype "passive"))
      (node (ref "C15") (pin "1") (pinfunction "1_1") (pintype "passive"))
      (node (ref "C16") (pin "P$1") (pinfunction "1_P$1") (pintype "passive"))
      (node (ref "D101") (pin "C") (pinfunction "C_C") (pintype "passive"))
      (node (ref "L102") (pin "1") (pinfunction "1_1") (pintype "passive"))
      (node (ref "L104") (pin "1") (pinfunction "1_1") (pintype "passive"))
      (node (ref "L3") (pin "1") (pinfunction "1_1") (pintype "passive"))
      (node (ref "L5") (pin "1") (pinfunction "1_1") (pintype "passive"))
      (node (ref "R128") (pin "P$2") (pinfunction "2_P$2") (pintype "passive"))
      (node (ref "R131") (pin "P$2") (pinfunction "2_P$2") (pintype "passive"))
      (node (ref "R137") (pin "P$1") (pinfunction "1_P$1") (pintype "passive"))
    )
    (net (code "45") (name "Net-(C126-2)") (class "Default")
      (node (ref "C126") (pin "P$2") (pinfunction "2_P$2") (pintype "passive"))
      (node (ref "C129") (pin "2") (pinfunction "2_2") (pintype "passive"))
      (node (ref "IC103") (pin "2") (pinfunction "VIN_2") (pintype "power_in"))
      (node (ref "IC103") (pin "3") (pinfunction "EN_3") (pintype "input"))
      (node (ref "L103") (pin "2") (pinfunction "2_2") (pintype "passive"))
    )
    (net (code "46") (name "Net-(C128-1)") (class "Default")
      (node (ref "C128") (pin "P$1") (pinfunction "1_P$1") (pintype "passive"))
      (node (ref "R119") (pin "P$1") (pinfunction "1_P$1") (pintype "passive"))
    )
    (net (code "47") (name "Net-(C128-2)") (class "Default")
      (node (ref "C128") (pin "P$2") (pinfunction "2_P$2") (pintype "passive"))
      (node (ref "IC103") (pin "4") (pinfunction "ADJ_4") (pintype "input"))
      (node (ref "R115") (pin "P$1") (pinfunction "1_P$1") (pintype "passive"))
      (node (ref "R117") (pin "P$2") (pinfunction "2_P$2") (pintype "passive"))
    )
    (net (code "48") (name "Net-(C130-2)") (class "Default")
      (node (ref "C127") (pin "2") (pinfunction "2_2") (pintype "passive"))
      (node (ref "C130") (pin "P$2") (pinfunction "2_P$2") (pintype "passive"))
      (node (ref "L103") (pin "1") (pinfunction "1_1") (pintype "passive"))
      (node (ref "PSU3") (pin "11") (pinfunction "-VOUT_11") (pintype "passive"))
    )
    (net (code "49") (name "Net-(C134-Pad1)") (class "Default")
      (node (ref "C134") (pin "1") (pinfunction "1_1") (pintype "passive"))
      (node (ref "D4") (pin "C") (pinfunction "C_C") (pintype "passive"))
      (node (ref "D5") (pin "C") (pinfunction "C_C") (pintype "passive"))
      (node (ref "K10") (pin "1") (pinfunction "1_1") (pintype "passive"))
    )
    (net (code "50") (name "Net-(C134-Pad2)") (class "Default")
      (node (ref "C134") (pin "2") (pinfunction "2_2") (pintype "passive"))
      (node (ref "C139") (pin "2") (pinfunction "2_2") (pintype "passive"))
      (node (ref "K10") (pin "2") (pinfunction "2_2") (pintype "passive"))
      (node (ref "K9") (pin "2") (pinfunction "2_2") (pintype "passive"))
      (node (ref "L105") (pin "1") (pinfunction "1_1") (pintype "passive"))
    )
    (net (code "51") (name "Net-(C139-Pad1)") (class "Default")
      (node (ref "C139") (pin "1") (pinfunction "1_1") (pintype "passive"))
      (node (ref "D2") (pin "C") (pinfunction "C_C") (pintype "passive"))
      (node (ref "D3") (pin "C") (pinfunction "C_C") (pintype "passive"))
      (node (ref "K9") (pin "1") (pinfunction "1_1") (pintype "passive"))
    )
    (net (code "52") (name "Net-(C147-1)") (class "Default")
      (node (ref "C147") (pin "P$1") (pinfunction "1_P$1") (pintype "passive"))
      (node (ref "IC106") (pin "4") (pinfunction "BYPASS_4") (pintype "passive"))
    )
    (net (code "53") (name "Net-(C150-1)") (class "Default")
      (node (ref "C149") (pin "2") (pinfunction "2_2") (pintype "passive"))
      (node (ref "C150") (pin "P$1") (pinfunction "1_P$1") (pintype "passive"))
      (node (ref "C151") (pin "P$1") (pinfunction "1_P$1") (pintype "passive"))
      (node (ref "C152") (pin "P$1") (pinfunction "1_P$1") (pintype "passive"))
      (node (ref "C153") (pin "P$1") (pinfunction "1_P$1") (pintype "passive"))
      (node (ref "C156") (pin "P$1") (pinfunction "1_P$1") (pintype "passive"))
      (node (ref "IC1") (pin "20") (pinfunction "VSS_20") (pintype "bidirectional"))
      (node (ref "IC105") (pin "5") (pinfunction "GNDB_5") (pintype "power_in"))
      (node (ref "X1") (pin "4") (pinfunction "4_4") (pintype "passive"))
      (node (ref "X1") (pin "S1") (pinfunction "S1_S1") (pintype "passive"))
      (node (ref "X1") (pin "S2") (pinfunction "S2_S2") (pintype "passive"))
    )
    (net (code "54") (name "Net-(C150-2)") (class "Default")
      (node (ref "C150") (pin "P$2") (pinfunction "2_P$2") (pintype "passive"))
      (node (ref "IC1") (pin "17") (pinfunction "VUSB_17") (pintype "bidirectional"))
    )
    (net (code "55") (name "Net-(C151-2)") (class "Default")
      (node (ref "C149") (pin "1") (pinfunction "1_1") (pintype "passive"))
      (node (ref "C151") (pin "P$2") (pinfunction "2_P$2") (pintype "passive"))
      (node (ref "IC1") (pin "1") (pinfunction "VDD_1") (pintype "bidirectional"))
      (node (ref "IC1") (pin "4") (pinfunction "~{RST}_4") (pintype "bidirectional"))
      (node (ref "IC105") (pin "7") (pinfunction "VDDB_7") (pintype "power_in"))
      (node (ref "L1") (pin "2") (pinfunction "2_2") (pintype "passive"))
      (node (ref "R1") (pin "P$2") (pinfunction "2_P$2") (pintype "passive"))
      (node (ref "R136") (pin "P$2") (pinfunction "2_P$2") (pintype "passive"))
      (node (ref "R2") (pin "P$2") (pinfunction "2_P$2") (pintype "passive"))
    )
    (net (code "56") (name "Net-(C152-2)") (class "Default")
      (node (ref "C152") (pin "P$2") (pinfunction "2_P$2") (pintype "passive"))
      (node (ref "IC1") (pin "2") (pinfunction "OSC1_2") (pintype "bidirectional"))
      (node (ref "Q1") (pin "2") (pinfunction "2_2") (pintype "passive"))
    )
    (net (code "57") (name "Net-(C153-2)") (class "Default")
      (node (ref "C153") (pin "P$2") (pinfunction "2_P$2") (pintype "passive"))
      (node (ref "IC1") (pin "3") (pinfunction "OSC2_3") (pintype "bidirectional"))
      (node (ref "Q1") (pin "1") (pinfunction "1_1") (pintype "passive"))
    )
    (net (code "58") (name "Net-(C156-2)") (class "Default")
      (node (ref "C156") (pin "P$2") (pinfunction "2_P$2") (pintype "passive"))
      (node (ref "L1") (pin "1") (pinfunction "1_1") (pintype "passive"))
      (node (ref "X1") (pin "1") (pinfunction "1_1") (pintype "passive"))
    )
    (net (code "59") (name "Net-(D1-PadC)") (class "Default")
      (node (ref "D1") (pin "C") (pinfunction "C_C") (pintype "passive"))
      (node (ref "SV100") (pin "9") (pinfunction "9_9") (pintype "passive"))
    )
    (net (code "60") (name "Net-(D2-PadA)") (class "Default")
      (node (ref "D2") (pin "A") (pinfunction "A_A") (pintype "passive"))
      (node (ref "Q101") (pin "C") (pinfunction "C_C") (pintype "passive"))
    )
    (net (code "61") (name "Net-(D4-PadA)") (class "Default")
      (node (ref "D4") (pin "A") (pinfunction "A_A") (pintype "passive"))
      (node (ref "Q100") (pin "C") (pinfunction "C_C") (pintype "passive"))
    )
    (net (code "62") (name "Net-(D101-PadA)") (class "Default")
      (node (ref "D101") (pin "A") (pinfunction "A_A") (pintype "passive"))
      (node (ref "K1") (pin "2") (pinfunction "2_2") (pintype "passive"))
    )
    (net (code "63") (name "Net-(IC1-D+)") (class "Default")
      (node (ref "IC1") (pin "19") (pinfunction "D+_19") (pintype "bidirectional"))
      (node (ref "X1") (pin "3") (pinfunction "3_3") (pintype "passive"))
    )
    (net (code "64") (name "Net-(IC1-D-)") (class "Default")
      (node (ref "IC1") (pin "18") (pinfunction "D-_18") (pintype "bidirectional"))
      (node (ref "X1") (pin "2") (pinfunction "2_2") (pintype "passive"))
    )
    (net (code "65") (name "Net-(IC1-GP6{slash}RX_LED)") (class "Default")
      (node (ref "IC1") (pin "6") (pinfunction "GP6/RX_LED_6") (pintype "bidirectional"))
      (node (ref "LED2") (pin "C") (pinfunction "C_C") (pintype "passive"))
    )
    (net (code "66") (name "Net-(IC1-GP7{slash}TX_LED)") (class "Default")
      (node (ref "IC1") (pin "5") (pinfunction "GP7/TX_LED_5") (pintype "bidirectional"))
      (node (ref "LED1") (pin "C") (pinfunction "C_C") (pintype "passive"))
    )
    (net (code "67") (name "Net-(IC1-RX)") (class "Default")
      (node (ref "IC1") (pin "12") (pinfunction "RX_12") (pintype "bidirectional"))
      (node (ref "IC105") (pin "6") (pinfunction "OUTB_6") (pintype "output"))
      (node (ref "R136") (pin "P$1") (pinfunction "1_P$1") (pintype "passive"))
    )
    (net (code "68") (name "Net-(IC1-TX)") (class "Default")
      (node (ref "IC1") (pin "10") (pinfunction "TX_10") (pintype "bidirectional"))
      (node (ref "R4") (pin "P$2") (pinfunction "2_P$2") (pintype "passive"))
    )
    (net (code "69") (name "Net-(IC2-+IN)") (class "Default")
      (node (ref "C135") (pin "1") (pinfunction "1_1") (pintype "passive"))
      (node (ref "IC2") (pin "1") (pinfunction "+IN_1") (pintype "input"))
      (node (ref "R129") (pin "P$2") (pinfunction "2_P$2") (pintype "passive"))
      (node (ref "R19") (pin "2") (pinfunction "2_2") (pintype "passive"))
    )
    (net (code "70") (name "Net-(IC2--IN)") (class "Default")
      (node (ref "C9") (pin "1") (pinfunction "1_1") (pintype "passive"))
      (node (ref "IC2") (pin "2") (pinfunction "-IN_2") (pintype "input"))
      (node (ref "R130") (pin "P$2") (pinfunction "2_P$2") (pintype "passive"))
      (node (ref "R8") (pin "1") (pinfunction "1_1") (pintype "passive"))
    )
    (net (code "71") (name "Net-(IC2-OUT)") (class "Default")
      (node (ref "C12") (pin "1") (pinfunction "1_1") (pintype "passive"))
      (node (ref "C9") (pin "2") (pinfunction "2_2") (pintype "passive"))
      (node (ref "IC2") (pin "6") (pinfunction "OUT_6") (pintype "output"))
      (node (ref "R10") (pin "2") (pinfunction "2_2") (pintype "passive"))
      (node (ref "R12") (pin "1") (pinfunction "1_1") (pintype "passive"))
      (node (ref "R14") (pin "2") (pinfunction "2_2") (pintype "passive"))
      (node (ref "R15") (pin "1") (pinfunction "1_1") (pintype "passive"))
      (node (ref "R16") (pin "2") (pinfunction "2_2") (pintype "passive"))
      (node (ref "R17") (pin "1") (pinfunction "1_1") (pintype "passive"))
      (node (ref "R9") (pin "1") (pinfunction "1_1") (pintype "passive"))
    )
    (net (code "72") (name "Net-(IC4-+IN)") (class "Default")
      (node (ref "C103") (pin "1") (pinfunction "1_1") (pintype "passive"))
      (node (ref "IC4") (pin "3") (pinfunction "+IN_3") (pintype "input"))
      (node (ref "R102") (pin "P$2") (pinfunction "2_P$2") (pintype "passive"))
      (node (ref "R27") (pin "2") (pinfunction "2_2") (pintype "passive"))
    )
    (net (code "73") (name "Net-(IC4--IN)") (class "Default")
      (node (ref "C22") (pin "1") (pinfunction "1_1") (pintype "passive"))
      (node (ref "IC4") (pin "2") (pinfunction "-IN_2") (pintype "input"))
      (node (ref "R101") (pin "P$2") (pinfunction "2_P$2") (pintype "passive"))
      (node (ref "R26") (pin "1") (pinfunction "1_1") (pintype "passive"))
    )
    (net (code "74") (name "Net-(IC4-OUT)") (class "Default")
      (node (ref "C22") (pin "2") (pinfunction "2_2") (pintype "passive"))
      (node (ref "IC4") (pin "6") (pinfunction "OUT_6") (pintype "output"))
      (node (ref "R23") (pin "1") (pinfunction "1_1") (pintype "passive"))
    )
    (net (code "75") (name "Net-(IC100-SCL2)") (class "Default")
      (node (ref "IC100") (pin "6") (pinfunction "SCL2_6") (pintype "power_in"))
      (node (ref "R28") (pin "P$1") (pinfunction "1_P$1") (pintype "passive"))
      (node (ref "U1") (pin "2") (pinfunction "SCL_2") (pintype "input"))
    )
    (net (code "76") (name "Net-(IC100-SDA2)") (class "Default")
      (node (ref "IC100") (pin "7") (pinfunction "SDA2_7") (pintype "power_in"))
      (node (ref "R29") (pin "P$1") (pinfunction "1_P$1") (pintype "passive"))
      (node (ref "U1") (pin "3") (pinfunction "SDA_3") (pintype "bidirectional"))
    )
    (net (code "77") (name "Net-(IC104-SCL2)") (class "Default")
      (node (ref "IC104") (pin "6") (pinfunction "SCL2_6") (pintype "power_in"))
      (node (ref "R135") (pin "P$1") (pinfunction "1_P$1") (pintype "passive"))
      (node (ref "U100") (pin "2") (pinfunction "SCL_2") (pintype "input"))
    )
    (net (code "78") (name "Net-(IC104-SDA2)") (class "Default")
      (node (ref "IC104") (pin "7") (pinfunction "SDA2_7") (pintype "power_in"))
      (node (ref "R134") (pin "P$1") (pinfunction "1_P$1") (pintype "passive"))
      (node (ref "U100") (pin "3") (pinfunction "SDA_3") (pintype "bidirectional"))
    )
    (net (code "79") (name "Net-(IC105-INA)") (class "Default")
      (node (ref "IC105") (pin "4") (pinfunction "INA_4") (pintype "input"))
      (node (ref "R133") (pin "P$2") (pinfunction "2_P$2") (pintype "passive"))
    )
    (net (code "80") (name "Net-(IC105-INB)") (class "Default")
      (node (ref "IC105") (pin "8") (pinfunction "INB_8") (pintype "input"))
      (node (ref "R4") (pin "P$1") (pinfunction "1_P$1") (pintype "passive"))
    )
    (net (code "81") (name "Net-(K11A-+)") (class "Default")
      (node (ref "K11") (pin "1") (pinfunction "+_1") (pintype "passive"))
      (node (ref "K16") (pin "6") (pinfunction "6_6") (pintype "passive"))
    )
    (net (code "82") (name "Net-(K11A--)") (class "Default")
      (node (ref "K11") (pin "8") (pinfunction "-_8") (pintype "passive"))
      (node (ref "K16") (pin "5") (pinfunction "5_5") (pintype "passive"))
    )
    (net (code "83") (name "Net-(K11B-P)") (class "Default")
      (node (ref "K11") (pin "3") (pinfunction "P_3") (pintype "passive"))
      (node (ref "X3") (pin "2") (pinfunction "2_2") (pintype "passive"))
      (node (ref "X3") (pin "3") (pinfunction "2_3") (pintype "passive"))
      (node (ref "X3") (pin "4") (pinfunction "2_4") (pintype "passive"))
      (node (ref "X3") (pin "5") (pinfunction "2_5") (pintype "passive"))
      (node (ref "X4") (pin "2") (pinfunction "2_2") (pintype "passive"))
      (node (ref "X4") (pin "3") (pinfunction "2_3") (pintype "passive"))
      (node (ref "X4") (pin "4") (pinfunction "2_4") (pintype "passive"))
      (node (ref "X4") (pin "5") (pinfunction "2_5") (pintype "passive"))
    )
    (net (code "84") (name "Net-(K11B-S)") (class "Default")
      (node (ref "K11") (pin "4") (pinfunction "S_4") (pintype "passive"))
      (node (ref "X6") (pin "2") (pinfunction "2_2") (pintype "passive"))
      (node (ref "X6") (pin "3") (pinfunction "2_3") (pintype "passive"))
      (node (ref "X6") (pin "4") (pinfunction "2_4") (pintype "passive"))
      (node (ref "X6") (pin "5") (pinfunction "2_5") (pintype "passive"))
      (node (ref "X8") (pin "2") (pinfunction "2_2") (pintype "passive"))
      (node (ref "X8") (pin "3") (pinfunction "2_3") (pintype "passive"))
      (node (ref "X8") (pin "4") (pinfunction "2_4") (pintype "passive"))
      (node (ref "X8") (pin "5") (pinfunction "2_5") (pintype "passive"))
    )
    (net (code "85") (name "Net-(K11C-P)") (class "Default")
      (node (ref "C-LO") (pin "P$1") (pinfunction "P$1_P$1") (pintype "passive"))
      (node (ref "K11") (pin "6") (pinfunction "P_6") (pintype "passive"))
      (node (ref "X4") (pin "1") (pinfunction "1_1") (pintype "passive"))
    )
    (net (code "86") (name "Net-(K15A-+)") (class "Default")
      (node (ref "K15") (pin "1") (pinfunction "+_1") (pintype "passive"))
      (node (ref "K16") (pin "2") (pinfunction "2_2") (pintype "passive"))
    )
    (net (code "87") (name "Net-(K15A--)") (class "Default")
      (node (ref "K15") (pin "8") (pinfunction "-_8") (pintype "passive"))
      (node (ref "K16") (pin "1") (pinfunction "1_1") (pintype "passive"))
    )
    (net (code "88") (name "Net-(K15B-O)") (class "Default")
      (node (ref "K15") (pin "2") (pinfunction "O_2") (pintype "passive"))
      (node (ref "K15") (pin "7") (pinfunction "O_7") (pintype "passive"))
      (node (ref "P-LB") (pin "P$1") (pinfunction "P$1_P$1") (pintype "passive"))
    )
    (net (code "89") (name "Net-(K15B-S)") (class "Default")
      (node (ref "K15") (pin "4") (pinfunction "S_4") (pintype "passive"))
      (node (ref "K15") (pin "5") (pinfunction "S_5") (pintype "passive"))
      (node (ref "P-LA") (pin "P$1") (pinfunction "P$1_P$1") (pintype "passive"))
    )
    (net (code "90") (name "Net-(K100A-+)") (class "Default")
      (node (ref "K100") (pin "1") (pinfunction "+_1") (pintype "passive"))
      (node (ref "K16") (pin "3") (pinfunction "3_3") (pintype "passive"))
    )
    (net (code "91") (name "Net-(K100A--)") (class "Default")
      (node (ref "K100") (pin "8") (pinfunction "-_8") (pintype "passive"))
      (node (ref "K16") (pin "4") (pinfunction "4_4") (pintype "passive"))
    )
    (net (code "92") (name "Net-(K100B-O)") (class "Default")
      (node (ref "K100") (pin "2") (pinfunction "O_2") (pintype "passive"))
      (node (ref "K100") (pin "5") (pinfunction "S_5") (pintype "passive"))
      (node (ref "K15") (pin "3") (pinfunction "P_3") (pintype "passive"))
      (node (ref "K15") (pin "6") (pinfunction "P_6") (pintype "passive"))
    )
    (net (code "93") (name "Net-(K100B-P)") (class "Default")
      (node (ref "K100") (pin "3") (pinfunction "P_3") (pintype "passive"))
      (node (ref "X8") (pin "1") (pinfunction "1_1") (pintype "passive"))
    )
    (net (code "94") (name "Net-(K100B-S)") (class "Default")
      (node (ref "K100") (pin "4") (pinfunction "S_4") (pintype "passive"))
      (node (ref "K100") (pin "7") (pinfunction "O_7") (pintype "passive"))
      (node (ref "P-COM") (pin "P$1") (pinfunction "P$1_P$1") (pintype "passive"))
    )
    (net (code "95") (name "Net-(K100C-P)") (class "Default")
      (node (ref "K100") (pin "6") (pinfunction "P_6") (pintype "passive"))
      (node (ref "K11") (pin "5") (pinfunction "S_5") (pintype "passive"))
      (node (ref "X6") (pin "1") (pinfunction "1_1") (pintype "passive"))
    )
    (net (code "96") (name "Net-(K101B-O)") (class "Default")
      (node (ref "C11") (pin "+") (pinfunction "+_+") (pintype "passive"))
      (node (ref "C3") (pin "+") (pinfunction "+_+") (pintype "passive"))
      (node (ref "C5") (pin "+") (pinfunction "+_+") (pintype "passive"))
      (node (ref "C8") (pin "+") (pinfunction "+_+") (pintype "passive"))
      (node (ref "K101") (pin "2") (pinfunction "O_2") (pintype "passive"))
      (node (ref "K101") (pin "7") (pinfunction "O_7") (pintype "passive"))
      (node (ref "K102") (pin "4") (pinfunction "S_4") (pintype "passive"))
      (node (ref "K102") (pin "5") (pinfunction "S_5") (pintype "passive"))
      (node (ref "R10") (pin "1") (pinfunction "1_1") (pintype "passive"))
      (node (ref "R12") (pin "2") (pinfunction "2_2") (pintype "passive"))
      (node (ref "R14") (pin "1") (pinfunction "1_1") (pintype "passive"))
      (node (ref "R15") (pin "2") (pinfunction "2_2") (pintype "passive"))
      (node (ref "R16") (pin "1") (pinfunction "1_1") (pintype "passive"))
      (node (ref "R17") (pin "2") (pinfunction "2_2") (pintype "passive"))
      (node (ref "R8") (pin "2") (pinfunction "2_2") (pintype "passive"))
      (node (ref "R9") (pin "2") (pinfunction "2_2") (pintype "passive"))
    )
    (net (code "97") (name "Net-(K101B-P)") (class "Default")
      (node (ref "K101") (pin "3") (pinfunction "P_3") (pintype "passive"))
      (node (ref "K101") (pin "6") (pinfunction "P_6") (pintype "passive"))
      (node (ref "K102") (pin "3") (pinfunction "P_3") (pintype "passive"))
      (node (ref "K102") (pin "6") (pinfunction "P_6") (pintype "passive"))
      (node (ref "X5") (pin "1") (pinfunction "1_1") (pintype "passive"))
    )
    (net (code "98") (name "Net-(LED5-C)") (class "Default")
      (node (ref "LED5") (pin "K") (pinfunction "C_K") (pintype "passive"))
      (node (ref "LED6") (pin "K") (pinfunction "C_K") (pintype "passive"))
      (node (ref "LED7") (pin "K") (pinfunction "C_K") (pintype "passive"))
      (node (ref "LED8") (pin "K") (pinfunction "C_K") (pintype "passive"))
      (node (ref "LED9") (pin "K") (pinfunction "C_K") (pintype "passive"))
      (node (ref "SV100") (pin "6") (pinfunction "6_6") (pintype "passive"))
    )
    (net (code "99") (name "Net-(LED10-C)") (class "Default")
      (node (ref "LED10") (pin "K") (pinfunction "C_K") (pintype "passive"))
      (node (ref "LED11") (pin "K") (pinfunction "C_K") (pintype "passive"))
      (node (ref "LED12") (pin "K") (pinfunction "C_K") (pintype "passive"))
      (node (ref "LED13") (pin "K") (pinfunction "C_K") (pintype "passive"))
      (node (ref "LED14") (pin "K") (pinfunction "C_K") (pintype "passive"))
      (node (ref "SV100") (pin "7") (pinfunction "7_7") (pintype "passive"))
    )
    (net (code "100") (name "Net-(OK100-C)") (class "Default")
      (node (ref "OK100") (pin "2") (pinfunction "C_2") (pintype "passive"))
      (node (ref "OK101") (pin "1") (pinfunction "A_1") (pintype "passive"))
    )
    (net (code "101") (name "Net-(OK100-COL)") (class "Default")
      (node (ref "OK100") (pin "4") (pinfunction "COL_4") (pintype "passive"))
      (node (ref "PSU2") (pin "3") (pinfunction "ENAB_3") (pintype "input"))
    )
    (net (code "102") (name "Net-(OK100-EMIT)") (class "Default")
      (node (ref "C136") (pin "2") (pinfunction "2_2") (pintype "passive"))
      (node (ref "L5") (pin "4") (pinfunction "4_4") (pintype "passive"))
      (node (ref "OK100") (pin "3") (pinfunction "EMIT_3") (pintype "passive"))
      (node (ref "PSU2") (pin "2") (pinfunction "VIN-_2") (pintype "power_in"))
    )
    (net (code "103") (name "Net-(OK101-COL)") (class "Default")
      (node (ref "OK101") (pin "4") (pinfunction "COL_4") (pintype "passive"))
      (node (ref "PSU1") (pin "3") (pinfunction "ENAB_3") (pintype "input"))
    )
    (net (code "104") (name "Net-(OK101-EMIT)") (class "Default")
      (node (ref "C157") (pin "2") (pinfunction "2_2") (pintype "passive"))
      (node (ref "L3") (pin "4") (pinfunction "4_4") (pintype "passive"))
      (node (ref "OK101") (pin "3") (pinfunction "EMIT_3") (pintype "passive"))
      (node (ref "PSU1") (pin "2") (pinfunction "VIN-_2") (pintype "power_in"))
    )
    (net (code "105") (name "Net-(PSU1-VIN+)") (class "Default")
      (node (ref "C157") (pin "1") (pinfunction "1_1") (pintype "passive"))
      (node (ref "L3") (pin "2") (pinfunction "2_2") (pintype "passive"))
      (node (ref "PSU1") (pin "1") (pinfunction "VIN+_1") (pintype "power_in"))
    )
    (net (code "106") (name "Net-(PSU1-VOUT+)") (class "Default")
      (node (ref "C155") (pin "1") (pinfunction "1_1") (pintype "passive"))
      (node (ref "L2") (pin "1") (pinfunction "1_1") (pintype "passive"))
      (node (ref "PSU1") (pin "4") (pinfunction "VOUT+_4") (pintype "power_in"))
    )
    (net (code "107") (name "Net-(PSU2-VIN+)") (class "Default")
      (node (ref "C136") (pin "1") (pinfunction "1_1") (pintype "passive"))
      (node (ref "L5") (pin "2") (pinfunction "2_2") (pintype "passive"))
      (node (ref "PSU2") (pin "1") (pinfunction "VIN+_1") (pintype "power_in"))
    )
    (net (code "108") (name "Net-(PSU2-VOUT-)") (class "Default")
      (node (ref "C145") (pin "2") (pinfunction "2_2") (pintype "passive"))
      (node (ref "L4") (pin "1") (pinfunction "1_1") (pintype "passive"))
      (node (ref "PSU2") (pin "6") (pinfunction "VOUT-_6") (pintype "power_in"))
    )
    (net (code "109") (name "Net-(R1-1)") (class "Default")
      (node (ref "LED1") (pin "A") (pinfunction "A_A") (pintype "passive"))
      (node (ref "R1") (pin "P$1") (pinfunction "1_P$1") (pintype "passive"))
    )
    (net (code "110") (name "Net-(R2-1)") (class "Default")
      (node (ref "LED2") (pin "A") (pinfunction "A_A") (pintype "passive"))
      (node (ref "R2") (pin "P$1") (pinfunction "1_P$1") (pintype "passive"))
    )
    (net (code "111") (name "Net-(R3-1)") (class "Default")
      (node (ref "LED3") (pin "A") (pinfunction "A_A") (pintype "passive"))
      (node (ref "R3") (pin "P$1") (pinfunction "1_P$1") (pintype "passive"))
    )
    (net (code "112") (name "Net-(R5-1)") (class "Default")
      (node (ref "LED4") (pin "C") (pinfunction "C_C") (pintype "passive"))
      (node (ref "R5") (pin "P$1") (pinfunction "1_P$1") (pintype "passive"))
    )
    (net (code "113") (name "Net-(R13-2)") (class "Default")
      (node (ref "D100") (pin "A") (pinfunction "A_A") (pintype "passive"))
      (node (ref "R13") (pin "P$2") (pinfunction "2_P$2") (pintype "passive"))
      (node (ref "R20") (pin "3") (pinfunction "A_3") (pintype "passive"))
    )
    (net (code "114") (name "Net-(R20-S)") (class "Default")
      (node (ref "R19") (pin "1") (pinfunction "1_1") (pintype "passive"))
      (node (ref "R20") (pin "2") (pinfunction "S_2") (pintype "passive"))
    )
    (net (code "115") (name "Net-(R21-1)") (class "Default")
      (node (ref "LED15") (pin "A") (pinfunction "A_A") (pintype "passive"))
      (node (ref "R21") (pin "P$1") (pinfunction "1_P$1") (pintype "passive"))
    )
    (net (code "116") (name "Net-(R22-1)") (class "Default")
      (node (ref "LED16") (pin "C") (pinfunction "C_C") (pintype "passive"))
      (node (ref "R22") (pin "P$1") (pinfunction "1_P$1") (pintype "passive"))
    )
    (net (code "117") (name "Net-(R24-S)") (class "Default")
      (node (ref "R24") (pin "2") (pinfunction "S_2") (pintype "passive"))
      (node (ref "R27") (pin "1") (pinfunction "1_1") (pintype "passive"))
    )
    (net (code "118") (name "Net-(R25-1)") (class "Default")
      (node (ref "LED17") (pin "A") (pinfunction "A_A") (pintype "passive"))
      (node (ref "R25") (pin "P$1") (pinfunction "1_P$1") (pintype "passive"))
    )
    (net (code "119") (name "Net-(R101-1)") (class "Default")
      (node (ref "R101") (pin "P$1") (pinfunction "1_P$1") (pintype "passive"))
      (node (ref "R30") (pin "1") (pinfunction "E_1") (pintype "passive"))
    )
    (net (code "120") (name "Net-(R102-1)") (class "Default")
      (node (ref "R102") (pin "P$1") (pinfunction "1_P$1") (pintype "passive"))
      (node (ref "U1") (pin "7") (pinfunction "VOUT_7") (pintype "output"))
    )
    (net (code "121") (name "Net-(R104-1)") (class "Default")
      (node (ref "L102") (pin "2") (pinfunction "2_2") (pintype "passive"))
      (node (ref "R104") (pin "P$1") (pinfunction "1_P$1") (pintype "passive"))
      (node (ref "R105") (pin "P$1") (pinfunction "1_P$1") (pintype "passive"))
    )
    (net (code "122") (name "Net-(R107-2)") (class "Default")
      (node (ref "R107") (pin "P$2") (pinfunction "2_P$2") (pintype "passive"))
      (node (ref "SV1") (pin "10") (pinfunction "10_10") (pintype "passive"))
    )
    (net (code "123") (name "Net-(R108-1)") (class "Default")
      (node (ref "R108") (pin "P$1") (pinfunction "1_P$1") (pintype "passive"))
      (node (ref "SV1") (pin "9") (pinfunction "9_9") (pintype "passive"))
    )
    (net (code "124") (name "Net-(R110-1)") (class "Default")
      (node (ref "R110") (pin "P$1") (pinfunction "1_P$1") (pintype "passive"))
      (node (ref "SV1") (pin "7") (pinfunction "7_7") (pintype "passive"))
    )
    (net (code "125") (name "Net-(R111-1)") (class "Default")
      (node (ref "L104") (pin "2") (pinfunction "2_2") (pintype "passive"))
      (node (ref "R111") (pin "P$1") (pinfunction "1_P$1") (pintype "passive"))
      (node (ref "R112") (pin "P$1") (pinfunction "1_P$1") (pintype "passive"))
    )
    (net (code "126") (name "Net-(R114-2)") (class "Default")
      (node (ref "R114") (pin "P$2") (pinfunction "2_P$2") (pintype "passive"))
      (node (ref "SV1") (pin "8") (pinfunction "8_8") (pintype "passive"))
    )
    (net (code "127") (name "Net-(R116-2)") (class "Default")
      (node (ref "R116") (pin "P$2") (pinfunction "2_P$2") (pintype "passive"))
      (node (ref "SV1") (pin "6") (pinfunction "6_6") (pintype "passive"))
    )
    (net (code "128") (name "Net-(R118-1)") (class "Default")
      (node (ref "R118") (pin "P$1") (pinfunction "1_P$1") (pintype "passive"))
      (node (ref "SV1") (pin "5") (pinfunction "5_5") (pintype "passive"))
    )
    (net (code "129") (name "Net-(R120-2)") (class "Default")
      (node (ref "R120") (pin "P$2") (pinfunction "2_P$2") (pintype "passive"))
      (node (ref "SV1") (pin "4") (pinfunction "4_4") (pintype "passive"))
    )
    (net (code "130") (name "Net-(R121-1)") (class "Default")
      (node (ref "R121") (pin "P$1") (pinfunction "1_P$1") (pintype "passive"))
      (node (ref "SV1") (pin "3") (pinfunction "3_3") (pintype "passive"))
    )
    (net (code "131") (name "Net-(R122-2)") (class "Default")
      (node (ref "R122") (pin "P$2") (pinfunction "2_P$2") (pintype "passive"))
      (node (ref "SV1") (pin "2") (pinfunction "2_2") (pintype "passive"))
    )
    (net (code "132") (name "Net-(R123-1)") (class "Default")
      (node (ref "R123") (pin "P$1") (pinfunction "1_P$1") (pintype "passive"))
      (node (ref "SV1") (pin "1") (pinfunction "1_1") (pintype "passive"))
    )
    (net (code "133") (name "Net-(R127-2)") (class "Default")
      (node (ref "Q100") (pin "B") (pinfunction "B_B") (pintype "passive"))
      (node (ref "R127") (pin "P$2") (pinfunction "2_P$2") (pintype "passive"))
    )
    (net (code "134") (name "Net-(R128-1)") (class "Default")
      (node (ref "L105") (pin "2") (pinfunction "2_2") (pintype "passive"))
      (node (ref "R128") (pin "P$1") (pinfunction "1_P$1") (pintype "passive"))
      (node (ref "R131") (pin "P$1") (pinfunction "1_P$1") (pintype "passive"))
    )
    (net (code "135") (name "Net-(R129-1)") (class "Default")
      (node (ref "R129") (pin "P$1") (pinfunction "1_P$1") (pintype "passive"))
      (node (ref "U100") (pin "7") (pinfunction "VOUT_7") (pintype "output"))
    )
    (net (code "136") (name "Net-(R130-1)") (class "Default")
      (node (ref "R130") (pin "P$1") (pinfunction "1_P$1") (pintype "passive"))
      (node (ref "R7") (pin "1") (pinfunction "E_1") (pintype "passive"))
    )
    (net (code "137") (name "Net-(R132-2)") (class "Default")
      (node (ref "Q101") (pin "B") (pinfunction "B_B") (pintype "passive"))
      (node (ref "R132") (pin "P$2") (pinfunction "2_P$2") (pintype "passive"))
    )
    (net (code "138") (name "Net-(R137-2)") (class "Default")
      (node (ref "K2") (pin "2") (pinfunction "2_2") (pintype "passive"))
      (node (ref "R137") (pin "P$2") (pinfunction "2_P$2") (pintype "passive"))
    )
    (net (code "139") (name "Net-(TL1-P$1)") (class "Default")
      (node (ref "LED10") (pin "A") (pinfunction "A_A") (pintype "passive"))
      (node (ref "LED8") (pin "A") (pinfunction "A_A") (pintype "passive"))
      (node (ref "SV100") (pin "1") (pinfunction "1_1") (pintype "passive"))
      (node (ref "TL1") (pin "1") (pinfunction "P$1_1") (pintype "passive"))
    )
    (net (code "140") (name "Net-(TL1-P$2)") (class "Default")
      (node (ref "D1") (pin "A") (pinfunction "A_A") (pintype "passive"))
      (node (ref "TL1") (pin "3") (pinfunction "P$2_3") (pintype "passive"))
      (node (ref "TL2") (pin "3") (pinfunction "P$2_3") (pintype "passive"))
      (node (ref "TL3") (pin "3") (pinfunction "P$2_3") (pintype "passive"))
      (node (ref "TL4") (pin "3") (pinfunction "P$2_3") (pintype "passive"))
      (node (ref "TL5") (pin "3") (pinfunction "P$2_3") (pintype "passive"))
    )
    (net (code "141") (name "Net-(TL2-P$1)") (class "Default")
      (node (ref "LED11") (pin "A") (pinfunction "A_A") (pintype "passive"))
      (node (ref "LED7") (pin "A") (pinfunction "A_A") (pintype "passive"))
      (node (ref "SV100") (pin "2") (pinfunction "2_2") (pintype "passive"))
      (node (ref "TL2") (pin "1") (pinfunction "P$1_1") (pintype "passive"))
    )
    (net (code "142") (name "Net-(TL3-P$1)") (class "Default")
      (node (ref "LED12") (pin "A") (pinfunction "A_A") (pintype "passive"))
      (node (ref "LED6") (pin "A") (pinfunction "A_A") (pintype "passive"))
      (node (ref "SV100") (pin "3") (pinfunction "3_3") (pintype "passive"))
      (node (ref "TL3") (pin "1") (pinfunction "P$1_1") (pintype "passive"))
    )
    (net (code "143") (name "Net-(TL4-P$1)") (class "Default")
      (node (ref "LED13") (pin "A") (pinfunction "A_A") (pintype "passive"))
      (node (ref "LED5") (pin "A") (pinfunction "A_A") (pintype "passive"))
      (node (ref "SV100") (pin "4") (pinfunction "4_4") (pintype "passive"))
      (node (ref "TL4") (pin "1") (pinfunction "P$1_1") (pintype "passive"))
    )
    (net (code "144") (name "Net-(TL5-P$1)") (class "Default")
      (node (ref "LED14") (pin "A") (pinfunction "A_A") (pintype "passive"))
      (node (ref "LED9") (pin "A") (pinfunction "A_A") (pintype "passive"))
      (node (ref "SV100") (pin "5") (pinfunction "5_5") (pintype "passive"))
      (node (ref "TL5") (pin "1") (pinfunction "P$1_1") (pintype "passive"))
    )
    (net (code "145") (name "Net-(X2-2-Pad3)") (class "Default")
      (node (ref "X2") (pin "2") (pinfunction "2_2") (pintype "passive"))
      (node (ref "X2") (pin "3") (pinfunction "2_3") (pintype "passive"))
      (node (ref "X2") (pin "4") (pinfunction "2_4") (pintype "passive"))
      (node (ref "X2") (pin "5") (pinfunction "2_5") (pintype "passive"))
      (node (ref "X5") (pin "2") (pinfunction "2_2") (pintype "passive"))
      (node (ref "X5") (pin "3") (pinfunction "2_3") (pintype "passive"))
      (node (ref "X5") (pin "4") (pinfunction "2_4") (pintype "passive"))
      (node (ref "X5") (pin "5") (pinfunction "2_5") (pintype "passive"))
    )
    (net (code "146") (name "Net-(X7-2-Pad3)") (class "Default")
      (node (ref "X7") (pin "2") (pinfunction "2_2") (pintype "passive"))
      (node (ref "X7") (pin "3") (pinfunction "2_3") (pintype "passive"))
      (node (ref "X7") (pin "4") (pinfunction "2_4") (pintype "passive"))
      (node (ref "X7") (pin "5") (pinfunction "2_5") (pintype "passive"))
      (node (ref "X9") (pin "2") (pinfunction "2_2") (pintype "passive"))
      (node (ref "X9") (pin "3") (pinfunction "2_3") (pintype "passive"))
      (node (ref "X9") (pin "4") (pinfunction "2_4") (pintype "passive"))
      (node (ref "X9") (pin "5") (pinfunction "2_5") (pintype "passive"))
    )
    (net (code "147") (name "PBIAS") (class "Default")
      (node (ref "IC3") (pin "4") (pinfunction "PD2(PCINT18/INT0)_4") (pintype "bidirectional"))
      (node (ref "OK100") (pin "1") (pinfunction "A_1") (pintype "passive"))
      (node (ref "R126") (pin "P$1") (pinfunction "1_P$1") (pintype "passive"))
    )
    (net (code "148") (name "RE1A") (class "Default")
      (node (ref "IC5") (pin "20") (pinfunction "OUT1_20") (pintype "bidirectional"))
      (node (ref "K26") (pin "1") (pinfunction "1_1") (pintype "passive"))
      (node (ref "RN2") (pin "2") (pinfunction "2_2") (pintype "passive"))
      (node (ref "RN3") (pin "2") (pinfunction "2_2") (pintype "passive"))
    )
    (net (code "149") (name "RE1B") (class "Default")
      (node (ref "IC5") (pin "19") (pinfunction "OUT2_19") (pintype "bidirectional"))
      (node (ref "K26") (pin "2") (pinfunction "2_2") (pintype "passive"))
      (node (ref "RN1") (pin "2") (pinfunction "2_2") (pintype "passive"))
      (node (ref "RN4") (pin "2") (pinfunction "2_2") (pintype "passive"))
    )
    (net (code "150") (name "RE2A") (class "Default")
      (node (ref "IC5") (pin "17") (pinfunction "OUT3_17") (pintype "bidirectional"))
      (node (ref "K26") (pin "3") (pinfunction "3_3") (pintype "passive"))
      (node (ref "RN2") (pin "3") (pinfunction "3_3") (pintype "passive"))
      (node (ref "RN3") (pin "3") (pinfunction "3_3") (pintype "passive"))
    )
    (net (code "151") (name "RE2B") (class "Default")
      (node (ref "IC5") (pin "16") (pinfunction "OUT4_16") (pintype "bidirectional"))
      (node (ref "K26") (pin "4") (pinfunction "4_4") (pintype "passive"))
      (node (ref "RN1") (pin "3") (pinfunction "3_3") (pintype "passive"))
      (node (ref "RN4") (pin "3") (pinfunction "3_3") (pintype "passive"))
    )
    (net (code "152") (name "RE3A") (class "Default")
      (node (ref "IC5") (pin "14") (pinfunction "OUT5_14") (pintype "bidirectional"))
      (node (ref "K26") (pin "5") (pinfunction "5_5") (pintype "passive"))
      (node (ref "RN2") (pin "4") (pinfunction "4_4") (pintype "passive"))
      (node (ref "RN3") (pin "4") (pinfunction "4_4") (pintype "passive"))
    )
    (net (code "153") (name "RE3B") (class "Default")
      (node (ref "IC5") (pin "13") (pinfunction "OUT6_13") (pintype "bidirectional"))
      (node (ref "K26") (pin "6") (pinfunction "6_6") (pintype "passive"))
      (node (ref "RN1") (pin "4") (pinfunction "4_4") (pintype "passive"))
      (node (ref "RN4") (pin "4") (pinfunction "4_4") (pintype "passive"))
    )
    (net (code "154") (name "RE4A") (class "Default")
      (node (ref "IC5") (pin "11") (pinfunction "OUT7_11") (pintype "bidirectional"))
      (node (ref "K101") (pin "8") (pinfunction "-_8") (pintype "passive"))
      (node (ref "K102") (pin "1") (pinfunction "+_1") (pintype "passive"))
      (node (ref "RN2") (pin "5") (pinfunction "5_5") (pintype "passive"))
      (node (ref "RN3") (pin "5") (pinfunction "5_5") (pintype "passive"))
    )
    (net (code "155") (name "RE4B") (class "Default")
      (node (ref "IC5") (pin "10") (pinfunction "OUT8_10") (pintype "bidirectional"))
      (node (ref "K101") (pin "1") (pinfunction "+_1") (pintype "passive"))
      (node (ref "K102") (pin "8") (pinfunction "-_8") (pintype "passive"))
      (node (ref "RN1") (pin "5") (pinfunction "5_5") (pintype "passive"))
      (node (ref "RN4") (pin "5") (pinfunction "5_5") (pintype "passive"))
    )
    (net (code "156") (name "RXD") (class "Default")
      (node (ref "IC105") (pin "2") (pinfunction "OUTA_2") (pintype "output"))
      (node (ref "IC3") (pin "2") (pinfunction "PD0(PCINT16/RXD)_2") (pintype "bidirectional"))
      (node (ref "R6") (pin "P$1") (pinfunction "1_P$1") (pintype "passive"))
    )
    (net (code "157") (name "SCL") (class "Default")
      (node (ref "IC100") (pin "3") (pinfunction "SCL1_3") (pintype "power_in"))
      (node (ref "IC104") (pin "3") (pinfunction "SCL1_3") (pintype "power_in"))
      (node (ref "IC3") (pin "28") (pinfunction "PC5(ADC5/PCINT13)_28") (pintype "bidirectional"))
      (node (ref "R124") (pin "P$1") (pinfunction "1_P$1") (pintype "passive"))
    )
    (net (code "158") (name "SDA") (class "Default")
      (node (ref "IC100") (pin "2") (pinfunction "SDA1_2") (pintype "power_in"))
      (node (ref "IC104") (pin "2") (pinfunction "SDA1_2") (pintype "power_in"))
      (node (ref "IC3") (pin "27") (pinfunction "PC4(ADC4/PCINT12)_27") (pintype "bidirectional"))
      (node (ref "R125") (pin "P$1") (pinfunction "1_P$1") (pintype "passive"))
    )
    (net (code "159") (name "TXD") (class "Default")
      (node (ref "IC3") (pin "3") (pinfunction "PD1(PCINT17/TXD)_3") (pintype "bidirectional"))
      (node (ref "R133") (pin "P$1") (pinfunction "1_P$1") (pintype "passive"))
    )
    (net (code "160") (name "unconnected-(H1-MOUNT-PadB3,2)") (class "Default")
      (node (ref "H1") (pin "B3,2") (pinfunction "MOUNT_B3,2") (pintype "passive"))
    )
    (net (code "161") (name "unconnected-(H2-MOUNT-PadB3,2)") (class "Default")
      (node (ref "H2") (pin "B3,2") (pinfunction "MOUNT_B3,2") (pintype "passive"))
    )
    (net (code "162") (name "unconnected-(H3-MOUNT-PadB3,2)") (class "Default")
      (node (ref "H3") (pin "B3,2") (pinfunction "MOUNT_B3,2") (pintype "passive"))
    )
    (net (code "163") (name "unconnected-(H4-MOUNT-PadB3,2)") (class "Default")
      (node (ref "H4") (pin "B3,2") (pinfunction "MOUNT_B3,2") (pintype "passive"))
    )
    (net (code "164") (name "unconnected-(H5-MOUNT-PadB3,2)") (class "Default")
      (node (ref "H5") (pin "B3,2") (pinfunction "MOUNT_B3,2") (pintype "passive"))
    )
    (net (code "165") (name "unconnected-(H6-MOUNT-PadB3,2)") (class "Default")
      (node (ref "H6") (pin "B3,2") (pinfunction "MOUNT_B3,2") (pintype "passive"))
    )
    (net (code "166") (name "unconnected-(H7-MOUNT-PadB3,2)") (class "Default")
      (node (ref "H7") (pin "B3,2") (pinfunction "MOUNT_B3,2") (pintype "passive"))
    )
    (net (code "167") (name "unconnected-(H8-MOUNT-PadB3,2)") (class "Default")
      (node (ref "H8") (pin "B3,2") (pinfunction "MOUNT_B3,2") (pintype "passive"))
    )
    (net (code "168") (name "unconnected-(H9-MOUNT-PadB3,2)") (class "Default")
      (node (ref "H9") (pin "B3,2") (pinfunction "MOUNT_B3,2") (pintype "passive"))
    )
    (net (code "169") (name "unconnected-(H10-MOUNT-PadB3,2)") (class "Default")
      (node (ref "H10") (pin "B3,2") (pinfunction "MOUNT_B3,2") (pintype "passive"))
    )
    (net (code "170") (name "unconnected-(H11-MOUNT-PadB3,2)") (class "Default")
      (node (ref "H11") (pin "B3,2") (pinfunction "MOUNT_B3,2") (pintype "passive"))
    )
    (net (code "171") (name "unconnected-(H12-MOUNT-PadB3,2)") (class "Default")
      (node (ref "H12") (pin "B3,2") (pinfunction "MOUNT_B3,2") (pintype "passive"))
    )
    (net (code "172") (name "unconnected-(H13-MOUNT-PadB3,2)") (class "Default")
      (node (ref "H13") (pin "B3,2") (pinfunction "MOUNT_B3,2") (pintype "passive"))
    )
    (net (code "173") (name "unconnected-(H14-MOUNT-PadB3,2)") (class "Default")
      (node (ref "H14") (pin "B3,2") (pinfunction "MOUNT_B3,2") (pintype "passive"))
    )
    (net (code "174") (name "unconnected-(H15-MOUNT-PadB3,2)") (class "Default")
      (node (ref "H15") (pin "B3,2") (pinfunction "MOUNT_B3,2") (pintype "passive"))
    )
    (net (code "175") (name "unconnected-(H16-MOUNT-PadB3,2)") (class "Default")
      (node (ref "H16") (pin "B3,2") (pinfunction "MOUNT_B3,2") (pintype "passive"))
    )
    (net (code "176") (name "unconnected-(IC1-G0{slash}SSPND-Pad16)") (class "Default")
      (node (ref "IC1") (pin "16") (pinfunction "G0/SSPND_16") (pintype "bidirectional"))
    )
    (net (code "177") (name "unconnected-(IC1-GP1{slash}USBCFG-Pad15)") (class "Default")
      (node (ref "IC1") (pin "15") (pinfunction "GP1/USBCFG_15") (pintype "bidirectional"))
    )
    (net (code "178") (name "unconnected-(IC1-GP2-Pad14)") (class "Default")
      (node (ref "IC1") (pin "14") (pinfunction "GP2_14") (pintype "bidirectional"))
    )
    (net (code "179") (name "unconnected-(IC1-GP3-Pad9)") (class "Default")
      (node (ref "IC1") (pin "9") (pinfunction "GP3_9") (pintype "bidirectional"))
    )
    (net (code "180") (name "unconnected-(IC1-GP4-Pad8)") (class "Default")
      (node (ref "IC1") (pin "8") (pinfunction "GP4_8") (pintype "bidirectional"))
    )
    (net (code "181") (name "unconnected-(IC1-GP5-Pad7)") (class "Default")
      (node (ref "IC1") (pin "7") (pinfunction "GP5_7") (pintype "bidirectional"))
    )
    (net (code "182") (name "unconnected-(IC1-~{CTS}-Pad13)") (class "Default")
      (node (ref "IC1") (pin "13") (pinfunction "~{CTS}_13") (pintype "bidirectional"))
    )
    (net (code "183") (name "unconnected-(IC1-~{RTS}-Pad11)") (class "Default")
      (node (ref "IC1") (pin "11") (pinfunction "~{RTS}_11") (pintype "bidirectional"))
    )
    (net (code "184") (name "unconnected-(IC3-AREF-Pad21)") (class "Default")
      (node (ref "IC3") (pin "21") (pinfunction "AREF_21") (pintype "input"))
    )
    (net (code "185") (name "unconnected-(IC5-DOUT-Pad7)") (class "Default")
      (node (ref "IC5") (pin "7") (pinfunction "DOUT_7") (pintype "output"))
    )
    (net (code "186") (name "unconnected-(IC5-NC-Pad8)") (class "Default")
      (node (ref "IC5") (pin "8") (pinfunction "NC_8") (pintype "no_connect"))
    )
    (net (code "187") (name "unconnected-(K11B-O-Pad2)") (class "Default")
      (node (ref "K11") (pin "2") (pinfunction "O_2") (pintype "passive"))
    )
    (net (code "188") (name "unconnected-(K11C-O-Pad7)") (class "Default")
      (node (ref "K11") (pin "7") (pinfunction "O_7") (pintype "passive"))
    )
    (net (code "189") (name "unconnected-(PSU1-TRIM-Pad6)") (class "Default")
      (node (ref "PSU1") (pin "6") (pinfunction "TRIM_6") (pintype "input"))
    )
    (net (code "190") (name "unconnected-(PSU2-TRIM-Pad5)") (class "Default")
      (node (ref "PSU2") (pin "5") (pinfunction "TRIM_5") (pintype "input"))
    )
    (net (code "191") (name "unconnected-(SV100-Pad8)") (class "Default")
      (node (ref "SV100") (pin "8") (pinfunction "8_8") (pintype "passive"))
    )
    (net (code "192") (name "unconnected-(SV100-Pad10)") (class "Default")
      (node (ref "SV100") (pin "10") (pinfunction "10_10") (pintype "passive"))
    )
  )
)
